# tongueboard.net
KiCad netlist of a schematic drawn in EAGLE
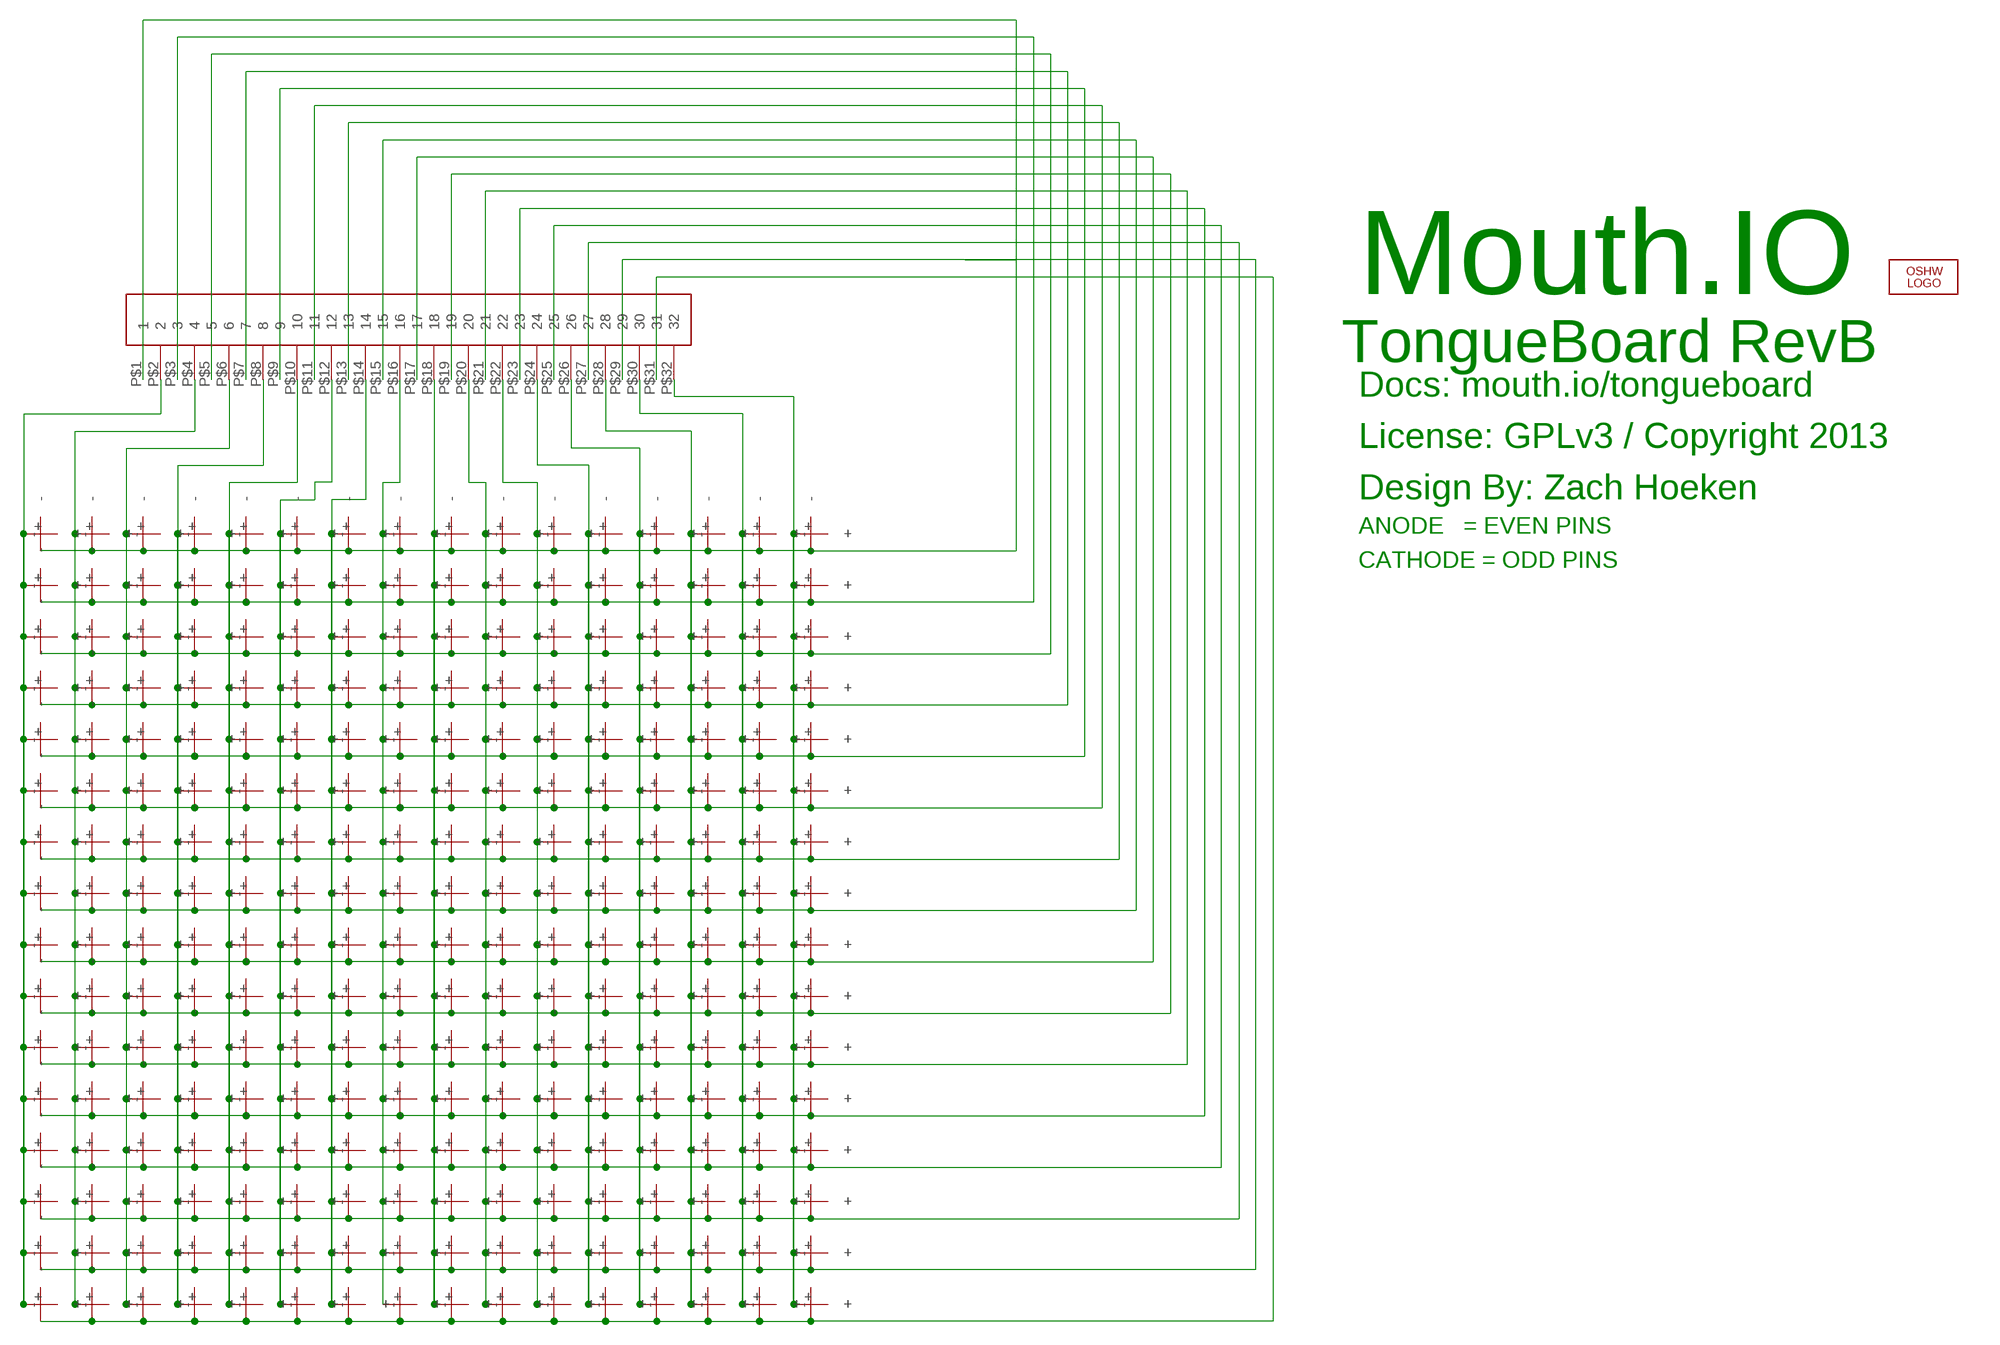
[diagram p0: schematic, sheet 1]

(export (version "E")
  (design (tool "Eeschema 10.0.6"))
  (components
    (comp (ref "LOGO1")
      (value "OSHW_LOGO_10MIL")
      (footprint "eagle-import:OSHW_10X500_NOTEXT_COPPER")
      (libsource (lib "eagle-import") (part "OSHW_LOGO_10MIL"))
    )
    (comp (ref "U$1")
      (value "ELECTRODE60MIL")
      (footprint "eagle-import:61MIL")
      (libsource (lib "eagle-import") (part "ELECTRODE60MIL"))
    )
    (comp (ref "U$2")
      (value "ELECTRODE60MIL")
      (footprint "eagle-import:61MIL")
      (libsource (lib "eagle-import") (part "ELECTRODE60MIL"))
    )
    (comp (ref "U$3")
      (value "ELECTRODE60MIL")
      (footprint "eagle-import:61MIL")
      (libsource (lib "eagle-import") (part "ELECTRODE60MIL"))
    )
    (comp (ref "U$4")
      (value "ELECTRODE60MIL")
      (footprint "eagle-import:61MIL")
      (libsource (lib "eagle-import") (part "ELECTRODE60MIL"))
    )
    (comp (ref "U$5")
      (value "ELECTRODE60MIL")
      (footprint "eagle-import:61MIL")
      (libsource (lib "eagle-import") (part "ELECTRODE60MIL"))
    )
    (comp (ref "U$6")
      (value "ELECTRODE60MIL")
      (footprint "eagle-import:61MIL")
      (libsource (lib "eagle-import") (part "ELECTRODE60MIL"))
    )
    (comp (ref "U$7")
      (value "ELECTRODE60MIL")
      (footprint "eagle-import:61MIL")
      (libsource (lib "eagle-import") (part "ELECTRODE60MIL"))
    )
    (comp (ref "U$8")
      (value "ELECTRODE60MIL")
      (footprint "eagle-import:61MIL")
      (libsource (lib "eagle-import") (part "ELECTRODE60MIL"))
    )
    (comp (ref "U$9")
      (value "ELECTRODE60MIL")
      (footprint "eagle-import:61MIL")
      (libsource (lib "eagle-import") (part "ELECTRODE60MIL"))
    )
    (comp (ref "U$10")
      (value "ELECTRODE60MIL")
      (footprint "eagle-import:61MIL")
      (libsource (lib "eagle-import") (part "ELECTRODE60MIL"))
    )
    (comp (ref "U$11")
      (value "ELECTRODE60MIL")
      (footprint "eagle-import:61MIL")
      (libsource (lib "eagle-import") (part "ELECTRODE60MIL"))
    )
    (comp (ref "U$12")
      (value "ELECTRODE60MIL")
      (footprint "eagle-import:61MIL")
      (libsource (lib "eagle-import") (part "ELECTRODE60MIL"))
    )
    (comp (ref "U$13")
      (value "ELECTRODE60MIL")
      (footprint "eagle-import:61MIL")
      (libsource (lib "eagle-import") (part "ELECTRODE60MIL"))
    )
    (comp (ref "U$14")
      (value "ELECTRODE60MIL")
      (footprint "eagle-import:61MIL")
      (libsource (lib "eagle-import") (part "ELECTRODE60MIL"))
    )
    (comp (ref "U$15")
      (value "ELECTRODE60MIL")
      (footprint "eagle-import:61MIL")
      (libsource (lib "eagle-import") (part "ELECTRODE60MIL"))
    )
    (comp (ref "U$16")
      (value "ELECTRODE61MILJCT")
      (footprint "eagle-import:61MILJCT")
      (libsource (lib "eagle-import") (part "ELECTRODE61MILJCT"))
    )
    (comp (ref "U$17")
      (value "ELECTRODE60MIL")
      (footprint "eagle-import:61MIL")
      (libsource (lib "eagle-import") (part "ELECTRODE60MIL"))
    )
    (comp (ref "U$18")
      (value "ELECTRODE60MIL")
      (footprint "eagle-import:61MIL")
      (libsource (lib "eagle-import") (part "ELECTRODE60MIL"))
    )
    (comp (ref "U$19")
      (value "ELECTRODE60MIL")
      (footprint "eagle-import:61MIL")
      (libsource (lib "eagle-import") (part "ELECTRODE60MIL"))
    )
    (comp (ref "U$20")
      (value "ELECTRODE60MIL")
      (footprint "eagle-import:61MIL")
      (libsource (lib "eagle-import") (part "ELECTRODE60MIL"))
    )
    (comp (ref "U$21")
      (value "ELECTRODE60MIL")
      (footprint "eagle-import:61MIL")
      (libsource (lib "eagle-import") (part "ELECTRODE60MIL"))
    )
    (comp (ref "U$22")
      (value "ELECTRODE60MIL")
      (footprint "eagle-import:61MIL")
      (libsource (lib "eagle-import") (part "ELECTRODE60MIL"))
    )
    (comp (ref "U$23")
      (value "ELECTRODE60MIL")
      (footprint "eagle-import:61MIL")
      (libsource (lib "eagle-import") (part "ELECTRODE60MIL"))
    )
    (comp (ref "U$24")
      (value "ELECTRODE60MIL")
      (footprint "eagle-import:61MIL")
      (libsource (lib "eagle-import") (part "ELECTRODE60MIL"))
    )
    (comp (ref "U$25")
      (value "ELECTRODE60MIL")
      (footprint "eagle-import:61MIL")
      (libsource (lib "eagle-import") (part "ELECTRODE60MIL"))
    )
    (comp (ref "U$26")
      (value "ELECTRODE60MIL")
      (footprint "eagle-import:61MIL")
      (libsource (lib "eagle-import") (part "ELECTRODE60MIL"))
    )
    (comp (ref "U$27")
      (value "ELECTRODE60MIL")
      (footprint "eagle-import:61MIL")
      (libsource (lib "eagle-import") (part "ELECTRODE60MIL"))
    )
    (comp (ref "U$28")
      (value "ELECTRODE60MIL")
      (footprint "eagle-import:61MIL")
      (libsource (lib "eagle-import") (part "ELECTRODE60MIL"))
    )
    (comp (ref "U$29")
      (value "ELECTRODE60MIL")
      (footprint "eagle-import:61MIL")
      (libsource (lib "eagle-import") (part "ELECTRODE60MIL"))
    )
    (comp (ref "U$30")
      (value "ELECTRODE60MIL")
      (footprint "eagle-import:61MIL")
      (libsource (lib "eagle-import") (part "ELECTRODE60MIL"))
    )
    (comp (ref "U$31")
      (value "ELECTRODE61MILJCT")
      (footprint "eagle-import:61MILJCT")
      (libsource (lib "eagle-import") (part "ELECTRODE61MILJCT"))
    )
    (comp (ref "U$32")
      (value "ELECTRODE60MIL")
      (footprint "eagle-import:61MIL")
      (libsource (lib "eagle-import") (part "ELECTRODE60MIL"))
    )
    (comp (ref "U$33")
      (value "ELECTRODE60MIL")
      (footprint "eagle-import:61MIL")
      (libsource (lib "eagle-import") (part "ELECTRODE60MIL"))
    )
    (comp (ref "U$34")
      (value "ELECTRODE60MIL")
      (footprint "eagle-import:61MIL")
      (libsource (lib "eagle-import") (part "ELECTRODE60MIL"))
    )
    (comp (ref "U$35")
      (value "ELECTRODE60MIL")
      (footprint "eagle-import:61MIL")
      (libsource (lib "eagle-import") (part "ELECTRODE60MIL"))
    )
    (comp (ref "U$36")
      (value "ELECTRODE60MIL")
      (footprint "eagle-import:61MIL")
      (libsource (lib "eagle-import") (part "ELECTRODE60MIL"))
    )
    (comp (ref "U$37")
      (value "ELECTRODE60MIL")
      (footprint "eagle-import:61MIL")
      (libsource (lib "eagle-import") (part "ELECTRODE60MIL"))
    )
    (comp (ref "U$38")
      (value "ELECTRODE60MIL")
      (footprint "eagle-import:61MIL")
      (libsource (lib "eagle-import") (part "ELECTRODE60MIL"))
    )
    (comp (ref "U$39")
      (value "ELECTRODE60MIL")
      (footprint "eagle-import:61MIL")
      (libsource (lib "eagle-import") (part "ELECTRODE60MIL"))
    )
    (comp (ref "U$40")
      (value "ELECTRODE60MIL")
      (footprint "eagle-import:61MIL")
      (libsource (lib "eagle-import") (part "ELECTRODE60MIL"))
    )
    (comp (ref "U$41")
      (value "ELECTRODE60MIL")
      (footprint "eagle-import:61MIL")
      (libsource (lib "eagle-import") (part "ELECTRODE60MIL"))
    )
    (comp (ref "U$42")
      (value "ELECTRODE60MIL")
      (footprint "eagle-import:61MIL")
      (libsource (lib "eagle-import") (part "ELECTRODE60MIL"))
    )
    (comp (ref "U$43")
      (value "ELECTRODE60MIL")
      (footprint "eagle-import:61MIL")
      (libsource (lib "eagle-import") (part "ELECTRODE60MIL"))
    )
    (comp (ref "U$44")
      (value "ELECTRODE60MIL")
      (footprint "eagle-import:61MIL")
      (libsource (lib "eagle-import") (part "ELECTRODE60MIL"))
    )
    (comp (ref "U$45")
      (value "ELECTRODE60MIL")
      (footprint "eagle-import:61MIL")
      (libsource (lib "eagle-import") (part "ELECTRODE60MIL"))
    )
    (comp (ref "U$46")
      (value "ELECTRODE61MILJCT")
      (footprint "eagle-import:61MILJCT")
      (libsource (lib "eagle-import") (part "ELECTRODE61MILJCT"))
    )
    (comp (ref "U$47")
      (value "ELECTRODE60MIL")
      (footprint "eagle-import:61MIL")
      (libsource (lib "eagle-import") (part "ELECTRODE60MIL"))
    )
    (comp (ref "U$48")
      (value "ELECTRODE60MIL")
      (footprint "eagle-import:61MIL")
      (libsource (lib "eagle-import") (part "ELECTRODE60MIL"))
    )
    (comp (ref "U$49")
      (value "ELECTRODE60MIL")
      (footprint "eagle-import:61MIL")
      (libsource (lib "eagle-import") (part "ELECTRODE60MIL"))
    )
    (comp (ref "U$50")
      (value "ELECTRODE60MIL")
      (footprint "eagle-import:61MIL")
      (libsource (lib "eagle-import") (part "ELECTRODE60MIL"))
    )
    (comp (ref "U$51")
      (value "ELECTRODE60MIL")
      (footprint "eagle-import:61MIL")
      (libsource (lib "eagle-import") (part "ELECTRODE60MIL"))
    )
    (comp (ref "U$52")
      (value "ELECTRODE60MIL")
      (footprint "eagle-import:61MIL")
      (libsource (lib "eagle-import") (part "ELECTRODE60MIL"))
    )
    (comp (ref "U$53")
      (value "ELECTRODE60MIL")
      (footprint "eagle-import:61MIL")
      (libsource (lib "eagle-import") (part "ELECTRODE60MIL"))
    )
    (comp (ref "U$54")
      (value "ELECTRODE60MIL")
      (footprint "eagle-import:61MIL")
      (libsource (lib "eagle-import") (part "ELECTRODE60MIL"))
    )
    (comp (ref "U$55")
      (value "ELECTRODE60MIL")
      (footprint "eagle-import:61MIL")
      (libsource (lib "eagle-import") (part "ELECTRODE60MIL"))
    )
    (comp (ref "U$56")
      (value "ELECTRODE60MIL")
      (footprint "eagle-import:61MIL")
      (libsource (lib "eagle-import") (part "ELECTRODE60MIL"))
    )
    (comp (ref "U$57")
      (value "ELECTRODE60MIL")
      (footprint "eagle-import:61MIL")
      (libsource (lib "eagle-import") (part "ELECTRODE60MIL"))
    )
    (comp (ref "U$58")
      (value "ELECTRODE60MIL")
      (footprint "eagle-import:61MIL")
      (libsource (lib "eagle-import") (part "ELECTRODE60MIL"))
    )
    (comp (ref "U$59")
      (value "ELECTRODE60MIL")
      (footprint "eagle-import:61MIL")
      (libsource (lib "eagle-import") (part "ELECTRODE60MIL"))
    )
    (comp (ref "U$60")
      (value "ELECTRODE60MIL")
      (footprint "eagle-import:61MIL")
      (libsource (lib "eagle-import") (part "ELECTRODE60MIL"))
    )
    (comp (ref "U$61")
      (value "ELECTRODE61MILJCT")
      (footprint "eagle-import:61MILJCT")
      (libsource (lib "eagle-import") (part "ELECTRODE61MILJCT"))
    )
    (comp (ref "U$62")
      (value "ELECTRODE60MIL")
      (footprint "eagle-import:61MIL")
      (libsource (lib "eagle-import") (part "ELECTRODE60MIL"))
    )
    (comp (ref "U$63")
      (value "ELECTRODE60MIL")
      (footprint "eagle-import:61MIL")
      (libsource (lib "eagle-import") (part "ELECTRODE60MIL"))
    )
    (comp (ref "U$64")
      (value "ELECTRODE60MIL")
      (footprint "eagle-import:61MIL")
      (libsource (lib "eagle-import") (part "ELECTRODE60MIL"))
    )
    (comp (ref "U$65")
      (value "ELECTRODE60MIL")
      (footprint "eagle-import:61MIL")
      (libsource (lib "eagle-import") (part "ELECTRODE60MIL"))
    )
    (comp (ref "U$66")
      (value "ELECTRODE60MIL")
      (footprint "eagle-import:61MIL")
      (libsource (lib "eagle-import") (part "ELECTRODE60MIL"))
    )
    (comp (ref "U$67")
      (value "ELECTRODE60MIL")
      (footprint "eagle-import:61MIL")
      (libsource (lib "eagle-import") (part "ELECTRODE60MIL"))
    )
    (comp (ref "U$68")
      (value "ELECTRODE60MIL")
      (footprint "eagle-import:61MIL")
      (libsource (lib "eagle-import") (part "ELECTRODE60MIL"))
    )
    (comp (ref "U$69")
      (value "ELECTRODE60MIL")
      (footprint "eagle-import:61MIL")
      (libsource (lib "eagle-import") (part "ELECTRODE60MIL"))
    )
    (comp (ref "U$70")
      (value "ELECTRODE60MIL")
      (footprint "eagle-import:61MIL")
      (libsource (lib "eagle-import") (part "ELECTRODE60MIL"))
    )
    (comp (ref "U$71")
      (value "ELECTRODE60MIL")
      (footprint "eagle-import:61MIL")
      (libsource (lib "eagle-import") (part "ELECTRODE60MIL"))
    )
    (comp (ref "U$72")
      (value "ELECTRODE60MIL")
      (footprint "eagle-import:61MIL")
      (libsource (lib "eagle-import") (part "ELECTRODE60MIL"))
    )
    (comp (ref "U$73")
      (value "ELECTRODE60MIL")
      (footprint "eagle-import:61MIL")
      (libsource (lib "eagle-import") (part "ELECTRODE60MIL"))
    )
    (comp (ref "U$74")
      (value "ELECTRODE60MIL")
      (footprint "eagle-import:61MIL")
      (libsource (lib "eagle-import") (part "ELECTRODE60MIL"))
    )
    (comp (ref "U$75")
      (value "ELECTRODE60MIL")
      (footprint "eagle-import:61MIL")
      (libsource (lib "eagle-import") (part "ELECTRODE60MIL"))
    )
    (comp (ref "U$76")
      (value "ELECTRODE61MILJCT")
      (footprint "eagle-import:61MILJCT")
      (libsource (lib "eagle-import") (part "ELECTRODE61MILJCT"))
    )
    (comp (ref "U$77")
      (value "ELECTRODE60MIL")
      (footprint "eagle-import:61MIL")
      (libsource (lib "eagle-import") (part "ELECTRODE60MIL"))
    )
    (comp (ref "U$78")
      (value "ELECTRODE60MIL")
      (footprint "eagle-import:61MIL")
      (libsource (lib "eagle-import") (part "ELECTRODE60MIL"))
    )
    (comp (ref "U$79")
      (value "ELECTRODE60MIL")
      (footprint "eagle-import:61MIL")
      (libsource (lib "eagle-import") (part "ELECTRODE60MIL"))
    )
    (comp (ref "U$80")
      (value "ELECTRODE60MIL")
      (footprint "eagle-import:61MIL")
      (libsource (lib "eagle-import") (part "ELECTRODE60MIL"))
    )
    (comp (ref "U$81")
      (value "ELECTRODE60MIL")
      (footprint "eagle-import:61MIL")
      (libsource (lib "eagle-import") (part "ELECTRODE60MIL"))
    )
    (comp (ref "U$82")
      (value "ELECTRODE60MIL")
      (footprint "eagle-import:61MIL")
      (libsource (lib "eagle-import") (part "ELECTRODE60MIL"))
    )
    (comp (ref "U$83")
      (value "ELECTRODE60MIL")
      (footprint "eagle-import:61MIL")
      (libsource (lib "eagle-import") (part "ELECTRODE60MIL"))
    )
    (comp (ref "U$84")
      (value "ELECTRODE60MIL")
      (footprint "eagle-import:61MIL")
      (libsource (lib "eagle-import") (part "ELECTRODE60MIL"))
    )
    (comp (ref "U$85")
      (value "ELECTRODE60MIL")
      (footprint "eagle-import:61MIL")
      (libsource (lib "eagle-import") (part "ELECTRODE60MIL"))
    )
    (comp (ref "U$86")
      (value "ELECTRODE60MIL")
      (footprint "eagle-import:61MIL")
      (libsource (lib "eagle-import") (part "ELECTRODE60MIL"))
    )
    (comp (ref "U$87")
      (value "ELECTRODE60MIL")
      (footprint "eagle-import:61MIL")
      (libsource (lib "eagle-import") (part "ELECTRODE60MIL"))
    )
    (comp (ref "U$88")
      (value "ELECTRODE60MIL")
      (footprint "eagle-import:61MIL")
      (libsource (lib "eagle-import") (part "ELECTRODE60MIL"))
    )
    (comp (ref "U$89")
      (value "ELECTRODE60MIL")
      (footprint "eagle-import:61MIL")
      (libsource (lib "eagle-import") (part "ELECTRODE60MIL"))
    )
    (comp (ref "U$90")
      (value "ELECTRODE60MIL")
      (footprint "eagle-import:61MIL")
      (libsource (lib "eagle-import") (part "ELECTRODE60MIL"))
    )
    (comp (ref "U$91")
      (value "ELECTRODE61MILJCT")
      (footprint "eagle-import:61MILJCT")
      (libsource (lib "eagle-import") (part "ELECTRODE61MILJCT"))
    )
    (comp (ref "U$92")
      (value "ELECTRODE60MIL")
      (footprint "eagle-import:61MIL")
      (libsource (lib "eagle-import") (part "ELECTRODE60MIL"))
    )
    (comp (ref "U$93")
      (value "ELECTRODE60MIL")
      (footprint "eagle-import:61MIL")
      (libsource (lib "eagle-import") (part "ELECTRODE60MIL"))
    )
    (comp (ref "U$94")
      (value "ELECTRODE60MIL")
      (footprint "eagle-import:61MIL")
      (libsource (lib "eagle-import") (part "ELECTRODE60MIL"))
    )
    (comp (ref "U$95")
      (value "ELECTRODE60MIL")
      (footprint "eagle-import:61MIL")
      (libsource (lib "eagle-import") (part "ELECTRODE60MIL"))
    )
    (comp (ref "U$96")
      (value "ELECTRODE60MIL")
      (footprint "eagle-import:61MIL")
      (libsource (lib "eagle-import") (part "ELECTRODE60MIL"))
    )
    (comp (ref "U$97")
      (value "ELECTRODE60MIL")
      (footprint "eagle-import:61MIL")
      (libsource (lib "eagle-import") (part "ELECTRODE60MIL"))
    )
    (comp (ref "U$98")
      (value "ELECTRODE60MIL")
      (footprint "eagle-import:61MIL")
      (libsource (lib "eagle-import") (part "ELECTRODE60MIL"))
    )
    (comp (ref "U$99")
      (value "ELECTRODE60MIL")
      (footprint "eagle-import:61MIL")
      (libsource (lib "eagle-import") (part "ELECTRODE60MIL"))
    )
    (comp (ref "U$100")
      (value "ELECTRODE60MIL")
      (footprint "eagle-import:61MIL")
      (libsource (lib "eagle-import") (part "ELECTRODE60MIL"))
    )
    (comp (ref "U$101")
      (value "ELECTRODE60MIL")
      (footprint "eagle-import:61MIL")
      (libsource (lib "eagle-import") (part "ELECTRODE60MIL"))
    )
    (comp (ref "U$102")
      (value "ELECTRODE60MIL")
      (footprint "eagle-import:61MIL")
      (libsource (lib "eagle-import") (part "ELECTRODE60MIL"))
    )
    (comp (ref "U$103")
      (value "ELECTRODE60MIL")
      (footprint "eagle-import:61MIL")
      (libsource (lib "eagle-import") (part "ELECTRODE60MIL"))
    )
    (comp (ref "U$104")
      (value "ELECTRODE60MIL")
      (footprint "eagle-import:61MIL")
      (libsource (lib "eagle-import") (part "ELECTRODE60MIL"))
    )
    (comp (ref "U$105")
      (value "ELECTRODE60MIL")
      (footprint "eagle-import:61MIL")
      (libsource (lib "eagle-import") (part "ELECTRODE60MIL"))
    )
    (comp (ref "U$106")
      (value "ELECTRODE61MILJCT")
      (footprint "eagle-import:61MILJCT")
      (libsource (lib "eagle-import") (part "ELECTRODE61MILJCT"))
    )
    (comp (ref "U$107")
      (value "ELECTRODE60MIL")
      (footprint "eagle-import:61MIL")
      (libsource (lib "eagle-import") (part "ELECTRODE60MIL"))
    )
    (comp (ref "U$108")
      (value "ELECTRODE60MIL")
      (footprint "eagle-import:61MIL")
      (libsource (lib "eagle-import") (part "ELECTRODE60MIL"))
    )
    (comp (ref "U$109")
      (value "ELECTRODE60MIL")
      (footprint "eagle-import:61MIL")
      (libsource (lib "eagle-import") (part "ELECTRODE60MIL"))
    )
    (comp (ref "U$110")
      (value "ELECTRODE60MIL")
      (footprint "eagle-import:61MIL")
      (libsource (lib "eagle-import") (part "ELECTRODE60MIL"))
    )
    (comp (ref "U$111")
      (value "ELECTRODE60MIL")
      (footprint "eagle-import:61MIL")
      (libsource (lib "eagle-import") (part "ELECTRODE60MIL"))
    )
    (comp (ref "U$112")
      (value "ELECTRODE60MIL")
      (footprint "eagle-import:61MIL")
      (libsource (lib "eagle-import") (part "ELECTRODE60MIL"))
    )
    (comp (ref "U$113")
      (value "ELECTRODE60MIL")
      (footprint "eagle-import:61MIL")
      (libsource (lib "eagle-import") (part "ELECTRODE60MIL"))
    )
    (comp (ref "U$114")
      (value "ELECTRODE60MIL")
      (footprint "eagle-import:61MIL")
      (libsource (lib "eagle-import") (part "ELECTRODE60MIL"))
    )
    (comp (ref "U$115")
      (value "ELECTRODE60MIL")
      (footprint "eagle-import:61MIL")
      (libsource (lib "eagle-import") (part "ELECTRODE60MIL"))
    )
    (comp (ref "U$116")
      (value "ELECTRODE60MIL")
      (footprint "eagle-import:61MIL")
      (libsource (lib "eagle-import") (part "ELECTRODE60MIL"))
    )
    (comp (ref "U$117")
      (value "ELECTRODE60MIL")
      (footprint "eagle-import:61MIL")
      (libsource (lib "eagle-import") (part "ELECTRODE60MIL"))
    )
    (comp (ref "U$118")
      (value "ELECTRODE60MIL")
      (footprint "eagle-import:61MIL")
      (libsource (lib "eagle-import") (part "ELECTRODE60MIL"))
    )
    (comp (ref "U$119")
      (value "ELECTRODE60MIL")
      (footprint "eagle-import:61MIL")
      (libsource (lib "eagle-import") (part "ELECTRODE60MIL"))
    )
    (comp (ref "U$120")
      (value "ELECTRODE60MIL")
      (footprint "eagle-import:61MIL")
      (libsource (lib "eagle-import") (part "ELECTRODE60MIL"))
    )
    (comp (ref "U$121")
      (value "ELECTRODE61MILJCT")
      (footprint "eagle-import:61MILJCT")
      (libsource (lib "eagle-import") (part "ELECTRODE61MILJCT"))
    )
    (comp (ref "U$122")
      (value "ELECTRODE60MIL")
      (footprint "eagle-import:61MIL")
      (libsource (lib "eagle-import") (part "ELECTRODE60MIL"))
    )
    (comp (ref "U$123")
      (value "ELECTRODE60MIL")
      (footprint "eagle-import:61MIL")
      (libsource (lib "eagle-import") (part "ELECTRODE60MIL"))
    )
    (comp (ref "U$124")
      (value "ELECTRODE60MIL")
      (footprint "eagle-import:61MIL")
      (libsource (lib "eagle-import") (part "ELECTRODE60MIL"))
    )
    (comp (ref "U$125")
      (value "ELECTRODE60MIL")
      (footprint "eagle-import:61MIL")
      (libsource (lib "eagle-import") (part "ELECTRODE60MIL"))
    )
    (comp (ref "U$126")
      (value "ELECTRODE60MIL")
      (footprint "eagle-import:61MIL")
      (libsource (lib "eagle-import") (part "ELECTRODE60MIL"))
    )
    (comp (ref "U$127")
      (value "ELECTRODE60MIL")
      (footprint "eagle-import:61MIL")
      (libsource (lib "eagle-import") (part "ELECTRODE60MIL"))
    )
    (comp (ref "U$128")
      (value "ELECTRODE60MIL")
      (footprint "eagle-import:61MIL")
      (libsource (lib "eagle-import") (part "ELECTRODE60MIL"))
    )
    (comp (ref "U$129")
      (value "ELECTRODE60MIL")
      (footprint "eagle-import:61MIL")
      (libsource (lib "eagle-import") (part "ELECTRODE60MIL"))
    )
    (comp (ref "U$130")
      (value "ELECTRODE60MIL")
      (footprint "eagle-import:61MIL")
      (libsource (lib "eagle-import") (part "ELECTRODE60MIL"))
    )
    (comp (ref "U$131")
      (value "ELECTRODE60MIL")
      (footprint "eagle-import:61MIL")
      (libsource (lib "eagle-import") (part "ELECTRODE60MIL"))
    )
    (comp (ref "U$132")
      (value "ELECTRODE60MIL")
      (footprint "eagle-import:61MIL")
      (libsource (lib "eagle-import") (part "ELECTRODE60MIL"))
    )
    (comp (ref "U$133")
      (value "ELECTRODE60MIL")
      (footprint "eagle-import:61MIL")
      (libsource (lib "eagle-import") (part "ELECTRODE60MIL"))
    )
    (comp (ref "U$134")
      (value "ELECTRODE60MIL")
      (footprint "eagle-import:61MIL")
      (libsource (lib "eagle-import") (part "ELECTRODE60MIL"))
    )
    (comp (ref "U$135")
      (value "ELECTRODE60MIL")
      (footprint "eagle-import:61MIL")
      (libsource (lib "eagle-import") (part "ELECTRODE60MIL"))
    )
    (comp (ref "U$136")
      (value "ELECTRODE61MILJCT")
      (footprint "eagle-import:61MILJCT")
      (libsource (lib "eagle-import") (part "ELECTRODE61MILJCT"))
    )
    (comp (ref "U$137")
      (value "ELECTRODE60MIL")
      (footprint "eagle-import:61MIL")
      (libsource (lib "eagle-import") (part "ELECTRODE60MIL"))
    )
    (comp (ref "U$138")
      (value "ELECTRODE60MIL")
      (footprint "eagle-import:61MIL")
      (libsource (lib "eagle-import") (part "ELECTRODE60MIL"))
    )
    (comp (ref "U$139")
      (value "ELECTRODE60MIL")
      (footprint "eagle-import:61MIL")
      (libsource (lib "eagle-import") (part "ELECTRODE60MIL"))
    )
    (comp (ref "U$140")
      (value "ELECTRODE60MIL")
      (footprint "eagle-import:61MIL")
      (libsource (lib "eagle-import") (part "ELECTRODE60MIL"))
    )
    (comp (ref "U$141")
      (value "ELECTRODE60MIL")
      (footprint "eagle-import:61MIL")
      (libsource (lib "eagle-import") (part "ELECTRODE60MIL"))
    )
    (comp (ref "U$142")
      (value "ELECTRODE60MIL")
      (footprint "eagle-import:61MIL")
      (libsource (lib "eagle-import") (part "ELECTRODE60MIL"))
    )
    (comp (ref "U$143")
      (value "ELECTRODE60MIL")
      (footprint "eagle-import:61MIL")
      (libsource (lib "eagle-import") (part "ELECTRODE60MIL"))
    )
    (comp (ref "U$144")
      (value "ELECTRODE60MIL")
      (footprint "eagle-import:61MIL")
      (libsource (lib "eagle-import") (part "ELECTRODE60MIL"))
    )
    (comp (ref "U$145")
      (value "ELECTRODE60MIL")
      (footprint "eagle-import:61MIL")
      (libsource (lib "eagle-import") (part "ELECTRODE60MIL"))
    )
    (comp (ref "U$146")
      (value "ELECTRODE60MIL")
      (footprint "eagle-import:61MIL")
      (libsource (lib "eagle-import") (part "ELECTRODE60MIL"))
    )
    (comp (ref "U$147")
      (value "ELECTRODE60MIL")
      (footprint "eagle-import:61MIL")
      (libsource (lib "eagle-import") (part "ELECTRODE60MIL"))
    )
    (comp (ref "U$148")
      (value "ELECTRODE60MIL")
      (footprint "eagle-import:61MIL")
      (libsource (lib "eagle-import") (part "ELECTRODE60MIL"))
    )
    (comp (ref "U$149")
      (value "ELECTRODE60MIL")
      (footprint "eagle-import:61MIL")
      (libsource (lib "eagle-import") (part "ELECTRODE60MIL"))
    )
    (comp (ref "U$150")
      (value "ELECTRODE60MIL")
      (footprint "eagle-import:61MIL")
      (libsource (lib "eagle-import") (part "ELECTRODE60MIL"))
    )
    (comp (ref "U$151")
      (value "ELECTRODE61MILJCT")
      (footprint "eagle-import:61MILJCT")
      (libsource (lib "eagle-import") (part "ELECTRODE61MILJCT"))
    )
    (comp (ref "U$152")
      (value "ELECTRODE60MIL")
      (footprint "eagle-import:61MIL")
      (libsource (lib "eagle-import") (part "ELECTRODE60MIL"))
    )
    (comp (ref "U$153")
      (value "ELECTRODE60MIL")
      (footprint "eagle-import:61MIL")
      (libsource (lib "eagle-import") (part "ELECTRODE60MIL"))
    )
    (comp (ref "U$154")
      (value "ELECTRODE60MIL")
      (footprint "eagle-import:61MIL")
      (libsource (lib "eagle-import") (part "ELECTRODE60MIL"))
    )
    (comp (ref "U$155")
      (value "ELECTRODE60MIL")
      (footprint "eagle-import:61MIL")
      (libsource (lib "eagle-import") (part "ELECTRODE60MIL"))
    )
    (comp (ref "U$156")
      (value "ELECTRODE60MIL")
      (footprint "eagle-import:61MIL")
      (libsource (lib "eagle-import") (part "ELECTRODE60MIL"))
    )
    (comp (ref "U$157")
      (value "ELECTRODE60MIL")
      (footprint "eagle-import:61MIL")
      (libsource (lib "eagle-import") (part "ELECTRODE60MIL"))
    )
    (comp (ref "U$158")
      (value "ELECTRODE60MIL")
      (footprint "eagle-import:61MIL")
      (libsource (lib "eagle-import") (part "ELECTRODE60MIL"))
    )
    (comp (ref "U$159")
      (value "ELECTRODE60MIL")
      (footprint "eagle-import:61MIL")
      (libsource (lib "eagle-import") (part "ELECTRODE60MIL"))
    )
    (comp (ref "U$160")
      (value "ELECTRODE60MIL")
      (footprint "eagle-import:61MIL")
      (libsource (lib "eagle-import") (part "ELECTRODE60MIL"))
    )
    (comp (ref "U$161")
      (value "ELECTRODE60MIL")
      (footprint "eagle-import:61MIL")
      (libsource (lib "eagle-import") (part "ELECTRODE60MIL"))
    )
    (comp (ref "U$162")
      (value "ELECTRODE60MIL")
      (footprint "eagle-import:61MIL")
      (libsource (lib "eagle-import") (part "ELECTRODE60MIL"))
    )
    (comp (ref "U$163")
      (value "ELECTRODE60MIL")
      (footprint "eagle-import:61MIL")
      (libsource (lib "eagle-import") (part "ELECTRODE60MIL"))
    )
    (comp (ref "U$164")
      (value "ELECTRODE60MIL")
      (footprint "eagle-import:61MIL")
      (libsource (lib "eagle-import") (part "ELECTRODE60MIL"))
    )
    (comp (ref "U$165")
      (value "ELECTRODE60MIL")
      (footprint "eagle-import:61MIL")
      (libsource (lib "eagle-import") (part "ELECTRODE60MIL"))
    )
    (comp (ref "U$166")
      (value "ELECTRODE61MILJCT")
      (footprint "eagle-import:61MILJCT")
      (libsource (lib "eagle-import") (part "ELECTRODE61MILJCT"))
    )
    (comp (ref "U$167")
      (value "ELECTRODE60MIL")
      (footprint "eagle-import:61MIL")
      (libsource (lib "eagle-import") (part "ELECTRODE60MIL"))
    )
    (comp (ref "U$168")
      (value "ELECTRODE60MIL")
      (footprint "eagle-import:61MIL")
      (libsource (lib "eagle-import") (part "ELECTRODE60MIL"))
    )
    (comp (ref "U$169")
      (value "ELECTRODE60MIL")
      (footprint "eagle-import:61MIL")
      (libsource (lib "eagle-import") (part "ELECTRODE60MIL"))
    )
    (comp (ref "U$170")
      (value "ELECTRODE60MIL")
      (footprint "eagle-import:61MIL")
      (libsource (lib "eagle-import") (part "ELECTRODE60MIL"))
    )
    (comp (ref "U$171")
      (value "ELECTRODE60MIL")
      (footprint "eagle-import:61MIL")
      (libsource (lib "eagle-import") (part "ELECTRODE60MIL"))
    )
    (comp (ref "U$172")
      (value "ELECTRODE60MIL")
      (footprint "eagle-import:61MIL")
      (libsource (lib "eagle-import") (part "ELECTRODE60MIL"))
    )
    (comp (ref "U$173")
      (value "ELECTRODE60MIL")
      (footprint "eagle-import:61MIL")
      (libsource (lib "eagle-import") (part "ELECTRODE60MIL"))
    )
    (comp (ref "U$174")
      (value "ELECTRODE60MIL")
      (footprint "eagle-import:61MIL")
      (libsource (lib "eagle-import") (part "ELECTRODE60MIL"))
    )
    (comp (ref "U$175")
      (value "ELECTRODE60MIL")
      (footprint "eagle-import:61MIL")
      (libsource (lib "eagle-import") (part "ELECTRODE60MIL"))
    )
    (comp (ref "U$176")
      (value "ELECTRODE60MIL")
      (footprint "eagle-import:61MIL")
      (libsource (lib "eagle-import") (part "ELECTRODE60MIL"))
    )
    (comp (ref "U$177")
      (value "ELECTRODE60MIL")
      (footprint "eagle-import:61MIL")
      (libsource (lib "eagle-import") (part "ELECTRODE60MIL"))
    )
    (comp (ref "U$178")
      (value "ELECTRODE60MIL")
      (footprint "eagle-import:61MIL")
      (libsource (lib "eagle-import") (part "ELECTRODE60MIL"))
    )
    (comp (ref "U$179")
      (value "ELECTRODE60MIL")
      (footprint "eagle-import:61MIL")
      (libsource (lib "eagle-import") (part "ELECTRODE60MIL"))
    )
    (comp (ref "U$180")
      (value "ELECTRODE60MIL")
      (footprint "eagle-import:61MIL")
      (libsource (lib "eagle-import") (part "ELECTRODE60MIL"))
    )
    (comp (ref "U$181")
      (value "ELECTRODE61MILJCT")
      (footprint "eagle-import:61MILJCT")
      (libsource (lib "eagle-import") (part "ELECTRODE61MILJCT"))
    )
    (comp (ref "U$182")
      (value "ELECTRODE60MIL")
      (footprint "eagle-import:61MIL")
      (libsource (lib "eagle-import") (part "ELECTRODE60MIL"))
    )
    (comp (ref "U$183")
      (value "ELECTRODE60MIL")
      (footprint "eagle-import:61MIL")
      (libsource (lib "eagle-import") (part "ELECTRODE60MIL"))
    )
    (comp (ref "U$184")
      (value "ELECTRODE60MIL")
      (footprint "eagle-import:61MIL")
      (libsource (lib "eagle-import") (part "ELECTRODE60MIL"))
    )
    (comp (ref "U$185")
      (value "ELECTRODE60MIL")
      (footprint "eagle-import:61MIL")
      (libsource (lib "eagle-import") (part "ELECTRODE60MIL"))
    )
    (comp (ref "U$186")
      (value "ELECTRODE60MIL")
      (footprint "eagle-import:61MIL")
      (libsource (lib "eagle-import") (part "ELECTRODE60MIL"))
    )
    (comp (ref "U$187")
      (value "ELECTRODE60MIL")
      (footprint "eagle-import:61MIL")
      (libsource (lib "eagle-import") (part "ELECTRODE60MIL"))
    )
    (comp (ref "U$188")
      (value "ELECTRODE60MIL")
      (footprint "eagle-import:61MIL")
      (libsource (lib "eagle-import") (part "ELECTRODE60MIL"))
    )
    (comp (ref "U$189")
      (value "ELECTRODE60MIL")
      (footprint "eagle-import:61MIL")
      (libsource (lib "eagle-import") (part "ELECTRODE60MIL"))
    )
    (comp (ref "U$190")
      (value "ELECTRODE60MIL")
      (footprint "eagle-import:61MIL")
      (libsource (lib "eagle-import") (part "ELECTRODE60MIL"))
    )
    (comp (ref "U$191")
      (value "ELECTRODE60MIL")
      (footprint "eagle-import:61MIL")
      (libsource (lib "eagle-import") (part "ELECTRODE60MIL"))
    )
    (comp (ref "U$192")
      (value "ELECTRODE60MIL")
      (footprint "eagle-import:61MIL")
      (libsource (lib "eagle-import") (part "ELECTRODE60MIL"))
    )
    (comp (ref "U$193")
      (value "ELECTRODE60MIL")
      (footprint "eagle-import:61MIL")
      (libsource (lib "eagle-import") (part "ELECTRODE60MIL"))
    )
    (comp (ref "U$194")
      (value "ELECTRODE60MIL")
      (footprint "eagle-import:61MIL")
      (libsource (lib "eagle-import") (part "ELECTRODE60MIL"))
    )
    (comp (ref "U$195")
      (value "ELECTRODE60MIL")
      (footprint "eagle-import:61MIL")
      (libsource (lib "eagle-import") (part "ELECTRODE60MIL"))
    )
    (comp (ref "U$196")
      (value "ELECTRODE61MILJCT")
      (footprint "eagle-import:61MILJCT")
      (libsource (lib "eagle-import") (part "ELECTRODE61MILJCT"))
    )
    (comp (ref "U$197")
      (value "ELECTRODE60MIL")
      (footprint "eagle-import:61MIL")
      (libsource (lib "eagle-import") (part "ELECTRODE60MIL"))
    )
    (comp (ref "U$198")
      (value "ELECTRODE60MIL")
      (footprint "eagle-import:61MIL")
      (libsource (lib "eagle-import") (part "ELECTRODE60MIL"))
    )
    (comp (ref "U$199")
      (value "ELECTRODE60MIL")
      (footprint "eagle-import:61MIL")
      (libsource (lib "eagle-import") (part "ELECTRODE60MIL"))
    )
    (comp (ref "U$200")
      (value "ELECTRODE60MIL")
      (footprint "eagle-import:61MIL")
      (libsource (lib "eagle-import") (part "ELECTRODE60MIL"))
    )
    (comp (ref "U$201")
      (value "ELECTRODE60MIL")
      (footprint "eagle-import:61MIL")
      (libsource (lib "eagle-import") (part "ELECTRODE60MIL"))
    )
    (comp (ref "U$202")
      (value "ELECTRODE60MIL")
      (footprint "eagle-import:61MIL")
      (libsource (lib "eagle-import") (part "ELECTRODE60MIL"))
    )
    (comp (ref "U$203")
      (value "ELECTRODE60MIL")
      (footprint "eagle-import:61MIL")
      (libsource (lib "eagle-import") (part "ELECTRODE60MIL"))
    )
    (comp (ref "U$204")
      (value "ELECTRODE60MIL")
      (footprint "eagle-import:61MIL")
      (libsource (lib "eagle-import") (part "ELECTRODE60MIL"))
    )
    (comp (ref "U$205")
      (value "ELECTRODE60MIL")
      (footprint "eagle-import:61MIL")
      (libsource (lib "eagle-import") (part "ELECTRODE60MIL"))
    )
    (comp (ref "U$206")
      (value "ELECTRODE60MIL")
      (footprint "eagle-import:61MIL")
      (libsource (lib "eagle-import") (part "ELECTRODE60MIL"))
    )
    (comp (ref "U$207")
      (value "ELECTRODE60MIL")
      (footprint "eagle-import:61MIL")
      (libsource (lib "eagle-import") (part "ELECTRODE60MIL"))
    )
    (comp (ref "U$208")
      (value "ELECTRODE60MIL")
      (footprint "eagle-import:61MIL")
      (libsource (lib "eagle-import") (part "ELECTRODE60MIL"))
    )
    (comp (ref "U$209")
      (value "ELECTRODE60MIL")
      (footprint "eagle-import:61MIL")
      (libsource (lib "eagle-import") (part "ELECTRODE60MIL"))
    )
    (comp (ref "U$210")
      (value "ELECTRODE60MIL")
      (footprint "eagle-import:61MIL")
      (libsource (lib "eagle-import") (part "ELECTRODE60MIL"))
    )
    (comp (ref "U$211")
      (value "ELECTRODE61MILJCT")
      (footprint "eagle-import:61MILJCT")
      (libsource (lib "eagle-import") (part "ELECTRODE61MILJCT"))
    )
    (comp (ref "U$212")
      (value "ELECTRODE60MIL")
      (footprint "eagle-import:61MIL")
      (libsource (lib "eagle-import") (part "ELECTRODE60MIL"))
    )
    (comp (ref "U$213")
      (value "ELECTRODE60MIL")
      (footprint "eagle-import:61MIL")
      (libsource (lib "eagle-import") (part "ELECTRODE60MIL"))
    )
    (comp (ref "U$214")
      (value "ELECTRODE60MIL")
      (footprint "eagle-import:61MIL")
      (libsource (lib "eagle-import") (part "ELECTRODE60MIL"))
    )
    (comp (ref "U$215")
      (value "ELECTRODE60MIL")
      (footprint "eagle-import:61MIL")
      (libsource (lib "eagle-import") (part "ELECTRODE60MIL"))
    )
    (comp (ref "U$216")
      (value "ELECTRODE60MIL")
      (footprint "eagle-import:61MIL")
      (libsource (lib "eagle-import") (part "ELECTRODE60MIL"))
    )
    (comp (ref "U$217")
      (value "ELECTRODE60MIL")
      (footprint "eagle-import:61MIL")
      (libsource (lib "eagle-import") (part "ELECTRODE60MIL"))
    )
    (comp (ref "U$218")
      (value "ELECTRODE60MIL")
      (footprint "eagle-import:61MIL")
      (libsource (lib "eagle-import") (part "ELECTRODE60MIL"))
    )
    (comp (ref "U$219")
      (value "ELECTRODE60MIL")
      (footprint "eagle-import:61MIL")
      (libsource (lib "eagle-import") (part "ELECTRODE60MIL"))
    )
    (comp (ref "U$220")
      (value "ELECTRODE60MIL")
      (footprint "eagle-import:61MIL")
      (libsource (lib "eagle-import") (part "ELECTRODE60MIL"))
    )
    (comp (ref "U$221")
      (value "ELECTRODE60MIL")
      (footprint "eagle-import:61MIL")
      (libsource (lib "eagle-import") (part "ELECTRODE60MIL"))
    )
    (comp (ref "U$222")
      (value "ELECTRODE60MIL")
      (footprint "eagle-import:61MIL")
      (libsource (lib "eagle-import") (part "ELECTRODE60MIL"))
    )
    (comp (ref "U$223")
      (value "ELECTRODE60MIL")
      (footprint "eagle-import:61MIL")
      (libsource (lib "eagle-import") (part "ELECTRODE60MIL"))
    )
    (comp (ref "U$224")
      (value "ELECTRODE60MIL")
      (footprint "eagle-import:61MIL")
      (libsource (lib "eagle-import") (part "ELECTRODE60MIL"))
    )
    (comp (ref "U$225")
      (value "ELECTRODE60MIL")
      (footprint "eagle-import:61MIL")
      (libsource (lib "eagle-import") (part "ELECTRODE60MIL"))
    )
    (comp (ref "U$226")
      (value "ELECTRODE61MILJCT")
      (footprint "eagle-import:61MILJCT")
      (libsource (lib "eagle-import") (part "ELECTRODE61MILJCT"))
    )
    (comp (ref "U$227")
      (value "ELECTRODE60MIL")
      (footprint "eagle-import:61MIL")
      (libsource (lib "eagle-import") (part "ELECTRODE60MIL"))
    )
    (comp (ref "U$228")
      (value "ELECTRODE60MIL")
      (footprint "eagle-import:61MIL")
      (libsource (lib "eagle-import") (part "ELECTRODE60MIL"))
    )
    (comp (ref "U$229")
      (value "ELECTRODE60MIL")
      (footprint "eagle-import:61MIL")
      (libsource (lib "eagle-import") (part "ELECTRODE60MIL"))
    )
    (comp (ref "U$230")
      (value "ELECTRODE60MIL")
      (footprint "eagle-import:61MIL")
      (libsource (lib "eagle-import") (part "ELECTRODE60MIL"))
    )
    (comp (ref "U$231")
      (value "ELECTRODE60MIL")
      (footprint "eagle-import:61MIL")
      (libsource (lib "eagle-import") (part "ELECTRODE60MIL"))
    )
    (comp (ref "U$232")
      (value "ELECTRODE60MIL")
      (footprint "eagle-import:61MIL")
      (libsource (lib "eagle-import") (part "ELECTRODE60MIL"))
    )
    (comp (ref "U$233")
      (value "ELECTRODE60MIL")
      (footprint "eagle-import:61MIL")
      (libsource (lib "eagle-import") (part "ELECTRODE60MIL"))
    )
    (comp (ref "U$234")
      (value "ELECTRODE60MIL")
      (footprint "eagle-import:61MIL")
      (libsource (lib "eagle-import") (part "ELECTRODE60MIL"))
    )
    (comp (ref "U$235")
      (value "ELECTRODE60MIL")
      (footprint "eagle-import:61MIL")
      (libsource (lib "eagle-import") (part "ELECTRODE60MIL"))
    )
    (comp (ref "U$236")
      (value "ELECTRODE60MIL")
      (footprint "eagle-import:61MIL")
      (libsource (lib "eagle-import") (part "ELECTRODE60MIL"))
    )
    (comp (ref "U$237")
      (value "ELECTRODE60MIL")
      (footprint "eagle-import:61MIL")
      (libsource (lib "eagle-import") (part "ELECTRODE60MIL"))
    )
    (comp (ref "U$238")
      (value "ELECTRODE60MIL")
      (footprint "eagle-import:61MIL")
      (libsource (lib "eagle-import") (part "ELECTRODE60MIL"))
    )
    (comp (ref "U$239")
      (value "ELECTRODE60MIL")
      (footprint "eagle-import:61MIL")
      (libsource (lib "eagle-import") (part "ELECTRODE60MIL"))
    )
    (comp (ref "U$240")
      (value "ELECTRODE60MIL")
      (footprint "eagle-import:61MIL")
      (libsource (lib "eagle-import") (part "ELECTRODE60MIL"))
    )
    (comp (ref "U$241")
      (value "ELECTRODE61MILJCT")
      (footprint "eagle-import:61MILJCT")
      (libsource (lib "eagle-import") (part "ELECTRODE61MILJCT"))
    )
    (comp (ref "U$242")
      (value "ELECTRODE60MIL")
      (footprint "eagle-import:61MIL")
      (libsource (lib "eagle-import") (part "ELECTRODE60MIL"))
    )
    (comp (ref "U$243")
      (value "ELECTRODE60MIL")
      (footprint "eagle-import:61MIL")
      (libsource (lib "eagle-import") (part "ELECTRODE60MIL"))
    )
    (comp (ref "U$244")
      (value "ELECTRODE60MIL")
      (footprint "eagle-import:61MIL")
      (libsource (lib "eagle-import") (part "ELECTRODE60MIL"))
    )
    (comp (ref "U$245")
      (value "ELECTRODE60MIL")
      (footprint "eagle-import:61MIL")
      (libsource (lib "eagle-import") (part "ELECTRODE60MIL"))
    )
    (comp (ref "U$246")
      (value "ELECTRODE60MIL")
      (footprint "eagle-import:61MIL")
      (libsource (lib "eagle-import") (part "ELECTRODE60MIL"))
    )
    (comp (ref "U$247")
      (value "ELECTRODE60MIL")
      (footprint "eagle-import:61MIL")
      (libsource (lib "eagle-import") (part "ELECTRODE60MIL"))
    )
    (comp (ref "U$248")
      (value "ELECTRODE60MIL")
      (footprint "eagle-import:61MIL")
      (libsource (lib "eagle-import") (part "ELECTRODE60MIL"))
    )
    (comp (ref "U$249")
      (value "ELECTRODE60MIL")
      (footprint "eagle-import:61MIL")
      (libsource (lib "eagle-import") (part "ELECTRODE60MIL"))
    )
    (comp (ref "U$250")
      (value "ELECTRODE60MIL")
      (footprint "eagle-import:61MIL")
      (libsource (lib "eagle-import") (part "ELECTRODE60MIL"))
    )
    (comp (ref "U$251")
      (value "ELECTRODE60MIL")
      (footprint "eagle-import:61MIL")
      (libsource (lib "eagle-import") (part "ELECTRODE60MIL"))
    )
    (comp (ref "U$252")
      (value "ELECTRODE60MIL")
      (footprint "eagle-import:61MIL")
      (libsource (lib "eagle-import") (part "ELECTRODE60MIL"))
    )
    (comp (ref "U$253")
      (value "ELECTRODE60MIL")
      (footprint "eagle-import:61MIL")
      (libsource (lib "eagle-import") (part "ELECTRODE60MIL"))
    )
    (comp (ref "U$254")
      (value "ELECTRODE60MIL")
      (footprint "eagle-import:61MIL")
      (libsource (lib "eagle-import") (part "ELECTRODE60MIL"))
    )
    (comp (ref "U$255")
      (value "ELECTRODE60MIL")
      (footprint "eagle-import:61MIL")
      (libsource (lib "eagle-import") (part "ELECTRODE60MIL"))
    )
    (comp (ref "U$256")
      (value "ELECTRODE60MIL")
      (footprint "eagle-import:61MIL")
      (libsource (lib "eagle-import") (part "ELECTRODE60MIL"))
    )
    (comp (ref "U$257")
      (value "FPC-0.5-32")
      (footprint "eagle-import:FPC-32-WIRE")
      (libsource (lib "eagle-import") (part "FPC-0.5-32"))
    )
  )
  (nets
    (net (code "1") (name "Net-(U$257-1)") (class "Default")
      (node (ref "U$241") (pin "-") (pinfunction "-_-") (pintype "bidirectional"))
      (node (ref "U$242") (pin "-") (pinfunction "-_-") (pintype "bidirectional"))
      (node (ref "U$243") (pin "-") (pinfunction "-_-") (pintype "bidirectional"))
      (node (ref "U$244") (pin "-") (pinfunction "-_-") (pintype "bidirectional"))
      (node (ref "U$245") (pin "-") (pinfunction "-_-") (pintype "bidirectional"))
      (node (ref "U$246") (pin "-") (pinfunction "-_-") (pintype "bidirectional"))
      (node (ref "U$247") (pin "-") (pinfunction "-_-") (pintype "bidirectional"))
      (node (ref "U$248") (pin "-") (pinfunction "-_-") (pintype "bidirectional"))
      (node (ref "U$249") (pin "-") (pinfunction "-_-") (pintype "bidirectional"))
      (node (ref "U$250") (pin "-") (pinfunction "-_-") (pintype "bidirectional"))
      (node (ref "U$251") (pin "-") (pinfunction "-_-") (pintype "bidirectional"))
      (node (ref "U$252") (pin "-") (pinfunction "-_-") (pintype "bidirectional"))
      (node (ref "U$253") (pin "-") (pinfunction "-_-") (pintype "bidirectional"))
      (node (ref "U$254") (pin "-") (pinfunction "-_-") (pintype "bidirectional"))
      (node (ref "U$255") (pin "-") (pinfunction "-_-") (pintype "bidirectional"))
      (node (ref "U$256") (pin "-") (pinfunction "-_-") (pintype "bidirectional"))
      (node (ref "U$257") (pin "P$1") (pinfunction "1_P$1") (pintype "bidirectional"))
    )
    (net (code "2") (name "Net-(U$257-2)") (class "Default")
      (node (ref "U$1") (pin "+") (pinfunction "+_+") (pintype "bidirectional"))
      (node (ref "U$113") (pin "+") (pinfunction "+_+") (pintype "bidirectional"))
      (node (ref "U$129") (pin "+") (pinfunction "+_+") (pintype "bidirectional"))
      (node (ref "U$145") (pin "+") (pinfunction "+_+") (pintype "bidirectional"))
      (node (ref "U$161") (pin "+") (pinfunction "+_+") (pintype "bidirectional"))
      (node (ref "U$17") (pin "+") (pinfunction "+_+") (pintype "bidirectional"))
      (node (ref "U$177") (pin "+") (pinfunction "+_+") (pintype "bidirectional"))
      (node (ref "U$193") (pin "+") (pinfunction "+_+") (pintype "bidirectional"))
      (node (ref "U$209") (pin "+") (pinfunction "+_+") (pintype "bidirectional"))
      (node (ref "U$225") (pin "+") (pinfunction "+_+") (pintype "bidirectional"))
      (node (ref "U$241") (pin "+") (pinfunction "+_+") (pintype "bidirectional"))
      (node (ref "U$257") (pin "P$2") (pinfunction "2_P$2") (pintype "bidirectional"))
      (node (ref "U$33") (pin "+") (pinfunction "+_+") (pintype "bidirectional"))
      (node (ref "U$49") (pin "+") (pinfunction "+_+") (pintype "bidirectional"))
      (node (ref "U$65") (pin "+") (pinfunction "+_+") (pintype "bidirectional"))
      (node (ref "U$81") (pin "+") (pinfunction "+_+") (pintype "bidirectional"))
      (node (ref "U$97") (pin "+") (pinfunction "+_+") (pintype "bidirectional"))
    )
    (net (code "3") (name "Net-(U$257-3)") (class "Default")
      (node (ref "U$225") (pin "-") (pinfunction "-_-") (pintype "bidirectional"))
      (node (ref "U$226") (pin "-") (pinfunction "-_-") (pintype "bidirectional"))
      (node (ref "U$227") (pin "-") (pinfunction "-_-") (pintype "bidirectional"))
      (node (ref "U$228") (pin "-") (pinfunction "-_-") (pintype "bidirectional"))
      (node (ref "U$229") (pin "-") (pinfunction "-_-") (pintype "bidirectional"))
      (node (ref "U$230") (pin "-") (pinfunction "-_-") (pintype "bidirectional"))
      (node (ref "U$231") (pin "-") (pinfunction "-_-") (pintype "bidirectional"))
      (node (ref "U$232") (pin "-") (pinfunction "-_-") (pintype "bidirectional"))
      (node (ref "U$233") (pin "-") (pinfunction "-_-") (pintype "bidirectional"))
      (node (ref "U$234") (pin "-") (pinfunction "-_-") (pintype "bidirectional"))
      (node (ref "U$235") (pin "-") (pinfunction "-_-") (pintype "bidirectional"))
      (node (ref "U$236") (pin "-") (pinfunction "-_-") (pintype "bidirectional"))
      (node (ref "U$237") (pin "-") (pinfunction "-_-") (pintype "bidirectional"))
      (node (ref "U$238") (pin "-") (pinfunction "-_-") (pintype "bidirectional"))
      (node (ref "U$239") (pin "-") (pinfunction "-_-") (pintype "bidirectional"))
      (node (ref "U$240") (pin "-") (pinfunction "-_-") (pintype "bidirectional"))
      (node (ref "U$257") (pin "P$3") (pinfunction "3_P$3") (pintype "bidirectional"))
    )
    (net (code "4") (name "Net-(U$257-4)") (class "Default")
      (node (ref "U$114") (pin "+") (pinfunction "+_+") (pintype "bidirectional"))
      (node (ref "U$130") (pin "+") (pinfunction "+_+") (pintype "bidirectional"))
      (node (ref "U$146") (pin "+") (pinfunction "+_+") (pintype "bidirectional"))
      (node (ref "U$162") (pin "+") (pinfunction "+_+") (pintype "bidirectional"))
      (node (ref "U$178") (pin "+") (pinfunction "+_+") (pintype "bidirectional"))
      (node (ref "U$18") (pin "+") (pinfunction "+_+") (pintype "bidirectional"))
      (node (ref "U$194") (pin "+") (pinfunction "+_+") (pintype "bidirectional"))
      (node (ref "U$2") (pin "+") (pinfunction "+_+") (pintype "bidirectional"))
      (node (ref "U$210") (pin "+") (pinfunction "+_+") (pintype "bidirectional"))
      (node (ref "U$226") (pin "+") (pinfunction "+_+") (pintype "bidirectional"))
      (node (ref "U$242") (pin "+") (pinfunction "+_+") (pintype "bidirectional"))
      (node (ref "U$257") (pin "P$4") (pinfunction "4_P$4") (pintype "bidirectional"))
      (node (ref "U$34") (pin "+") (pinfunction "+_+") (pintype "bidirectional"))
      (node (ref "U$50") (pin "+") (pinfunction "+_+") (pintype "bidirectional"))
      (node (ref "U$66") (pin "+") (pinfunction "+_+") (pintype "bidirectional"))
      (node (ref "U$82") (pin "+") (pinfunction "+_+") (pintype "bidirectional"))
      (node (ref "U$98") (pin "+") (pinfunction "+_+") (pintype "bidirectional"))
    )
    (net (code "5") (name "Net-(U$257-5)") (class "Default")
      (node (ref "U$209") (pin "-") (pinfunction "-_-") (pintype "bidirectional"))
      (node (ref "U$210") (pin "-") (pinfunction "-_-") (pintype "bidirectional"))
      (node (ref "U$211") (pin "-") (pinfunction "-_-") (pintype "bidirectional"))
      (node (ref "U$212") (pin "-") (pinfunction "-_-") (pintype "bidirectional"))
      (node (ref "U$213") (pin "-") (pinfunction "-_-") (pintype "bidirectional"))
      (node (ref "U$214") (pin "-") (pinfunction "-_-") (pintype "bidirectional"))
      (node (ref "U$215") (pin "-") (pinfunction "-_-") (pintype "bidirectional"))
      (node (ref "U$216") (pin "-") (pinfunction "-_-") (pintype "bidirectional"))
      (node (ref "U$217") (pin "-") (pinfunction "-_-") (pintype "bidirectional"))
      (node (ref "U$218") (pin "-") (pinfunction "-_-") (pintype "bidirectional"))
      (node (ref "U$219") (pin "-") (pinfunction "-_-") (pintype "bidirectional"))
      (node (ref "U$220") (pin "-") (pinfunction "-_-") (pintype "bidirectional"))
      (node (ref "U$221") (pin "-") (pinfunction "-_-") (pintype "bidirectional"))
      (node (ref "U$222") (pin "-") (pinfunction "-_-") (pintype "bidirectional"))
      (node (ref "U$223") (pin "-") (pinfunction "-_-") (pintype "bidirectional"))
      (node (ref "U$224") (pin "-") (pinfunction "-_-") (pintype "bidirectional"))
      (node (ref "U$257") (pin "P$5") (pinfunction "5_P$5") (pintype "bidirectional"))
    )
    (net (code "6") (name "Net-(U$257-6)") (class "Default")
      (node (ref "U$115") (pin "+") (pinfunction "+_+") (pintype "bidirectional"))
      (node (ref "U$131") (pin "+") (pinfunction "+_+") (pintype "bidirectional"))
      (node (ref "U$147") (pin "+") (pinfunction "+_+") (pintype "bidirectional"))
      (node (ref "U$163") (pin "+") (pinfunction "+_+") (pintype "bidirectional"))
      (node (ref "U$179") (pin "+") (pinfunction "+_+") (pintype "bidirectional"))
      (node (ref "U$19") (pin "+") (pinfunction "+_+") (pintype "bidirectional"))
      (node (ref "U$195") (pin "+") (pinfunction "+_+") (pintype "bidirectional"))
      (node (ref "U$211") (pin "+") (pinfunction "+_+") (pintype "bidirectional"))
      (node (ref "U$227") (pin "+") (pinfunction "+_+") (pintype "bidirectional"))
      (node (ref "U$243") (pin "+") (pinfunction "+_+") (pintype "bidirectional"))
      (node (ref "U$257") (pin "P$6") (pinfunction "6_P$6") (pintype "bidirectional"))
      (node (ref "U$3") (pin "+") (pinfunction "+_+") (pintype "bidirectional"))
      (node (ref "U$35") (pin "+") (pinfunction "+_+") (pintype "bidirectional"))
      (node (ref "U$51") (pin "+") (pinfunction "+_+") (pintype "bidirectional"))
      (node (ref "U$67") (pin "+") (pinfunction "+_+") (pintype "bidirectional"))
      (node (ref "U$83") (pin "+") (pinfunction "+_+") (pintype "bidirectional"))
      (node (ref "U$99") (pin "+") (pinfunction "+_+") (pintype "bidirectional"))
    )
    (net (code "7") (name "Net-(U$257-7)") (class "Default")
      (node (ref "U$193") (pin "-") (pinfunction "-_-") (pintype "bidirectional"))
      (node (ref "U$194") (pin "-") (pinfunction "-_-") (pintype "bidirectional"))
      (node (ref "U$195") (pin "-") (pinfunction "-_-") (pintype "bidirectional"))
      (node (ref "U$196") (pin "-") (pinfunction "-_-") (pintype "bidirectional"))
      (node (ref "U$197") (pin "-") (pinfunction "-_-") (pintype "bidirectional"))
      (node (ref "U$198") (pin "-") (pinfunction "-_-") (pintype "bidirectional"))
      (node (ref "U$199") (pin "-") (pinfunction "-_-") (pintype "bidirectional"))
      (node (ref "U$200") (pin "-") (pinfunction "-_-") (pintype "bidirectional"))
      (node (ref "U$201") (pin "-") (pinfunction "-_-") (pintype "bidirectional"))
      (node (ref "U$202") (pin "-") (pinfunction "-_-") (pintype "bidirectional"))
      (node (ref "U$203") (pin "-") (pinfunction "-_-") (pintype "bidirectional"))
      (node (ref "U$204") (pin "-") (pinfunction "-_-") (pintype "bidirectional"))
      (node (ref "U$205") (pin "-") (pinfunction "-_-") (pintype "bidirectional"))
      (node (ref "U$206") (pin "-") (pinfunction "-_-") (pintype "bidirectional"))
      (node (ref "U$207") (pin "-") (pinfunction "-_-") (pintype "bidirectional"))
      (node (ref "U$208") (pin "-") (pinfunction "-_-") (pintype "bidirectional"))
      (node (ref "U$257") (pin "P$7") (pinfunction "7_P$7") (pintype "bidirectional"))
    )
    (net (code "8") (name "Net-(U$257-8)") (class "Default")
      (node (ref "U$100") (pin "+") (pinfunction "+_+") (pintype "bidirectional"))
      (node (ref "U$116") (pin "+") (pinfunction "+_+") (pintype "bidirectional"))
      (node (ref "U$132") (pin "+") (pinfunction "+_+") (pintype "bidirectional"))
      (node (ref "U$148") (pin "+") (pinfunction "+_+") (pintype "bidirectional"))
      (node (ref "U$164") (pin "+") (pinfunction "+_+") (pintype "bidirectional"))
      (node (ref "U$180") (pin "+") (pinfunction "+_+") (pintype "bidirectional"))
      (node (ref "U$196") (pin "+") (pinfunction "+_+") (pintype "bidirectional"))
      (node (ref "U$20") (pin "+") (pinfunction "+_+") (pintype "bidirectional"))
      (node (ref "U$212") (pin "+") (pinfunction "+_+") (pintype "bidirectional"))
      (node (ref "U$228") (pin "+") (pinfunction "+_+") (pintype "bidirectional"))
      (node (ref "U$244") (pin "+") (pinfunction "+_+") (pintype "bidirectional"))
      (node (ref "U$257") (pin "P$8") (pinfunction "8_P$8") (pintype "bidirectional"))
      (node (ref "U$36") (pin "+") (pinfunction "+_+") (pintype "bidirectional"))
      (node (ref "U$4") (pin "+") (pinfunction "+_+") (pintype "bidirectional"))
      (node (ref "U$52") (pin "+") (pinfunction "+_+") (pintype "bidirectional"))
      (node (ref "U$68") (pin "+") (pinfunction "+_+") (pintype "bidirectional"))
      (node (ref "U$84") (pin "+") (pinfunction "+_+") (pintype "bidirectional"))
    )
    (net (code "9") (name "Net-(U$257-9)") (class "Default")
      (node (ref "U$177") (pin "-") (pinfunction "-_-") (pintype "bidirectional"))
      (node (ref "U$178") (pin "-") (pinfunction "-_-") (pintype "bidirectional"))
      (node (ref "U$179") (pin "-") (pinfunction "-_-") (pintype "bidirectional"))
      (node (ref "U$180") (pin "-") (pinfunction "-_-") (pintype "bidirectional"))
      (node (ref "U$181") (pin "-") (pinfunction "-_-") (pintype "bidirectional"))
      (node (ref "U$182") (pin "-") (pinfunction "-_-") (pintype "bidirectional"))
      (node (ref "U$183") (pin "-") (pinfunction "-_-") (pintype "bidirectional"))
      (node (ref "U$184") (pin "-") (pinfunction "-_-") (pintype "bidirectional"))
      (node (ref "U$185") (pin "-") (pinfunction "-_-") (pintype "bidirectional"))
      (node (ref "U$186") (pin "-") (pinfunction "-_-") (pintype "bidirectional"))
      (node (ref "U$187") (pin "-") (pinfunction "-_-") (pintype "bidirectional"))
      (node (ref "U$188") (pin "-") (pinfunction "-_-") (pintype "bidirectional"))
      (node (ref "U$189") (pin "-") (pinfunction "-_-") (pintype "bidirectional"))
      (node (ref "U$190") (pin "-") (pinfunction "-_-") (pintype "bidirectional"))
      (node (ref "U$191") (pin "-") (pinfunction "-_-") (pintype "bidirectional"))
      (node (ref "U$192") (pin "-") (pinfunction "-_-") (pintype "bidirectional"))
      (node (ref "U$257") (pin "P$9") (pinfunction "9_P$9") (pintype "bidirectional"))
    )
    (net (code "10") (name "Net-(U$257-10)") (class "Default")
      (node (ref "U$101") (pin "+") (pinfunction "+_+") (pintype "bidirectional"))
      (node (ref "U$117") (pin "+") (pinfunction "+_+") (pintype "bidirectional"))
      (node (ref "U$133") (pin "+") (pinfunction "+_+") (pintype "bidirectional"))
      (node (ref "U$149") (pin "+") (pinfunction "+_+") (pintype "bidirectional"))
      (node (ref "U$165") (pin "+") (pinfunction "+_+") (pintype "bidirectional"))
      (node (ref "U$181") (pin "+") (pinfunction "+_+") (pintype "bidirectional"))
      (node (ref "U$197") (pin "+") (pinfunction "+_+") (pintype "bidirectional"))
      (node (ref "U$21") (pin "+") (pinfunction "+_+") (pintype "bidirectional"))
      (node (ref "U$213") (pin "+") (pinfunction "+_+") (pintype "bidirectional"))
      (node (ref "U$229") (pin "+") (pinfunction "+_+") (pintype "bidirectional"))
      (node (ref "U$245") (pin "+") (pinfunction "+_+") (pintype "bidirectional"))
      (node (ref "U$257") (pin "P$10") (pinfunction "10_P$10") (pintype "bidirectional"))
      (node (ref "U$37") (pin "+") (pinfunction "+_+") (pintype "bidirectional"))
      (node (ref "U$5") (pin "+") (pinfunction "+_+") (pintype "bidirectional"))
      (node (ref "U$53") (pin "+") (pinfunction "+_+") (pintype "bidirectional"))
      (node (ref "U$69") (pin "+") (pinfunction "+_+") (pintype "bidirectional"))
      (node (ref "U$85") (pin "+") (pinfunction "+_+") (pintype "bidirectional"))
    )
    (net (code "11") (name "Net-(U$257-11)") (class "Default")
      (node (ref "U$161") (pin "-") (pinfunction "-_-") (pintype "bidirectional"))
      (node (ref "U$162") (pin "-") (pinfunction "-_-") (pintype "bidirectional"))
      (node (ref "U$163") (pin "-") (pinfunction "-_-") (pintype "bidirectional"))
      (node (ref "U$164") (pin "-") (pinfunction "-_-") (pintype "bidirectional"))
      (node (ref "U$165") (pin "-") (pinfunction "-_-") (pintype "bidirectional"))
      (node (ref "U$166") (pin "-") (pinfunction "-_-") (pintype "bidirectional"))
      (node (ref "U$167") (pin "-") (pinfunction "-_-") (pintype "bidirectional"))
      (node (ref "U$168") (pin "-") (pinfunction "-_-") (pintype "bidirectional"))
      (node (ref "U$169") (pin "-") (pinfunction "-_-") (pintype "bidirectional"))
      (node (ref "U$170") (pin "-") (pinfunction "-_-") (pintype "bidirectional"))
      (node (ref "U$171") (pin "-") (pinfunction "-_-") (pintype "bidirectional"))
      (node (ref "U$172") (pin "-") (pinfunction "-_-") (pintype "bidirectional"))
      (node (ref "U$173") (pin "-") (pinfunction "-_-") (pintype "bidirectional"))
      (node (ref "U$174") (pin "-") (pinfunction "-_-") (pintype "bidirectional"))
      (node (ref "U$175") (pin "-") (pinfunction "-_-") (pintype "bidirectional"))
      (node (ref "U$176") (pin "-") (pinfunction "-_-") (pintype "bidirectional"))
      (node (ref "U$257") (pin "P$11") (pinfunction "11_P$11") (pintype "bidirectional"))
    )
    (net (code "12") (name "Net-(U$257-12)") (class "Default")
      (node (ref "U$102") (pin "+") (pinfunction "+_+") (pintype "bidirectional"))
      (node (ref "U$118") (pin "+") (pinfunction "+_+") (pintype "bidirectional"))
      (node (ref "U$134") (pin "+") (pinfunction "+_+") (pintype "bidirectional"))
      (node (ref "U$150") (pin "+") (pinfunction "+_+") (pintype "bidirectional"))
      (node (ref "U$166") (pin "+") (pinfunction "+_+") (pintype "bidirectional"))
      (node (ref "U$182") (pin "+") (pinfunction "+_+") (pintype "bidirectional"))
      (node (ref "U$198") (pin "+") (pinfunction "+_+") (pintype "bidirectional"))
      (node (ref "U$214") (pin "+") (pinfunction "+_+") (pintype "bidirectional"))
      (node (ref "U$22") (pin "+") (pinfunction "+_+") (pintype "bidirectional"))
      (node (ref "U$230") (pin "+") (pinfunction "+_+") (pintype "bidirectional"))
      (node (ref "U$246") (pin "+") (pinfunction "+_+") (pintype "bidirectional"))
      (node (ref "U$257") (pin "P$12") (pinfunction "12_P$12") (pintype "bidirectional"))
      (node (ref "U$38") (pin "+") (pinfunction "+_+") (pintype "bidirectional"))
      (node (ref "U$54") (pin "+") (pinfunction "+_+") (pintype "bidirectional"))
      (node (ref "U$6") (pin "+") (pinfunction "+_+") (pintype "bidirectional"))
      (node (ref "U$70") (pin "+") (pinfunction "+_+") (pintype "bidirectional"))
      (node (ref "U$86") (pin "+") (pinfunction "+_+") (pintype "bidirectional"))
    )
    (net (code "13") (name "Net-(U$257-13)") (class "Default")
      (node (ref "U$145") (pin "-") (pinfunction "-_-") (pintype "bidirectional"))
      (node (ref "U$146") (pin "-") (pinfunction "-_-") (pintype "bidirectional"))
      (node (ref "U$147") (pin "-") (pinfunction "-_-") (pintype "bidirectional"))
      (node (ref "U$148") (pin "-") (pinfunction "-_-") (pintype "bidirectional"))
      (node (ref "U$149") (pin "-") (pinfunction "-_-") (pintype "bidirectional"))
      (node (ref "U$150") (pin "-") (pinfunction "-_-") (pintype "bidirectional"))
      (node (ref "U$151") (pin "-") (pinfunction "-_-") (pintype "bidirectional"))
      (node (ref "U$152") (pin "-") (pinfunction "-_-") (pintype "bidirectional"))
      (node (ref "U$153") (pin "-") (pinfunction "-_-") (pintype "bidirectional"))
      (node (ref "U$154") (pin "-") (pinfunction "-_-") (pintype "bidirectional"))
      (node (ref "U$155") (pin "-") (pinfunction "-_-") (pintype "bidirectional"))
      (node (ref "U$156") (pin "-") (pinfunction "-_-") (pintype "bidirectional"))
      (node (ref "U$157") (pin "-") (pinfunction "-_-") (pintype "bidirectional"))
      (node (ref "U$158") (pin "-") (pinfunction "-_-") (pintype "bidirectional"))
      (node (ref "U$159") (pin "-") (pinfunction "-_-") (pintype "bidirectional"))
      (node (ref "U$160") (pin "-") (pinfunction "-_-") (pintype "bidirectional"))
      (node (ref "U$257") (pin "P$13") (pinfunction "13_P$13") (pintype "bidirectional"))
    )
    (net (code "14") (name "Net-(U$257-14)") (class "Default")
      (node (ref "U$103") (pin "+") (pinfunction "+_+") (pintype "bidirectional"))
      (node (ref "U$119") (pin "+") (pinfunction "+_+") (pintype "bidirectional"))
      (node (ref "U$135") (pin "+") (pinfunction "+_+") (pintype "bidirectional"))
      (node (ref "U$151") (pin "+") (pinfunction "+_+") (pintype "bidirectional"))
      (node (ref "U$167") (pin "+") (pinfunction "+_+") (pintype "bidirectional"))
      (node (ref "U$183") (pin "+") (pinfunction "+_+") (pintype "bidirectional"))
      (node (ref "U$199") (pin "+") (pinfunction "+_+") (pintype "bidirectional"))
      (node (ref "U$215") (pin "+") (pinfunction "+_+") (pintype "bidirectional"))
      (node (ref "U$23") (pin "+") (pinfunction "+_+") (pintype "bidirectional"))
      (node (ref "U$231") (pin "+") (pinfunction "+_+") (pintype "bidirectional"))
      (node (ref "U$247") (pin "+") (pinfunction "+_+") (pintype "bidirectional"))
      (node (ref "U$257") (pin "P$14") (pinfunction "14_P$14") (pintype "bidirectional"))
      (node (ref "U$39") (pin "+") (pinfunction "+_+") (pintype "bidirectional"))
      (node (ref "U$55") (pin "+") (pinfunction "+_+") (pintype "bidirectional"))
      (node (ref "U$7") (pin "+") (pinfunction "+_+") (pintype "bidirectional"))
      (node (ref "U$71") (pin "+") (pinfunction "+_+") (pintype "bidirectional"))
      (node (ref "U$87") (pin "+") (pinfunction "+_+") (pintype "bidirectional"))
    )
    (net (code "15") (name "Net-(U$257-15)") (class "Default")
      (node (ref "U$129") (pin "-") (pinfunction "-_-") (pintype "bidirectional"))
      (node (ref "U$130") (pin "-") (pinfunction "-_-") (pintype "bidirectional"))
      (node (ref "U$131") (pin "-") (pinfunction "-_-") (pintype "bidirectional"))
      (node (ref "U$132") (pin "-") (pinfunction "-_-") (pintype "bidirectional"))
      (node (ref "U$133") (pin "-") (pinfunction "-_-") (pintype "bidirectional"))
      (node (ref "U$134") (pin "-") (pinfunction "-_-") (pintype "bidirectional"))
      (node (ref "U$135") (pin "-") (pinfunction "-_-") (pintype "bidirectional"))
      (node (ref "U$136") (pin "-") (pinfunction "-_-") (pintype "bidirectional"))
      (node (ref "U$137") (pin "-") (pinfunction "-_-") (pintype "bidirectional"))
      (node (ref "U$138") (pin "-") (pinfunction "-_-") (pintype "bidirectional"))
      (node (ref "U$139") (pin "-") (pinfunction "-_-") (pintype "bidirectional"))
      (node (ref "U$140") (pin "-") (pinfunction "-_-") (pintype "bidirectional"))
      (node (ref "U$141") (pin "-") (pinfunction "-_-") (pintype "bidirectional"))
      (node (ref "U$142") (pin "-") (pinfunction "-_-") (pintype "bidirectional"))
      (node (ref "U$143") (pin "-") (pinfunction "-_-") (pintype "bidirectional"))
      (node (ref "U$144") (pin "-") (pinfunction "-_-") (pintype "bidirectional"))
      (node (ref "U$257") (pin "P$15") (pinfunction "15_P$15") (pintype "bidirectional"))
    )
    (net (code "16") (name "Net-(U$257-16)") (class "Default")
      (node (ref "U$104") (pin "+") (pinfunction "+_+") (pintype "bidirectional"))
      (node (ref "U$120") (pin "+") (pinfunction "+_+") (pintype "bidirectional"))
      (node (ref "U$136") (pin "+") (pinfunction "+_+") (pintype "bidirectional"))
      (node (ref "U$152") (pin "+") (pinfunction "+_+") (pintype "bidirectional"))
      (node (ref "U$168") (pin "+") (pinfunction "+_+") (pintype "bidirectional"))
      (node (ref "U$184") (pin "+") (pinfunction "+_+") (pintype "bidirectional"))
      (node (ref "U$200") (pin "+") (pinfunction "+_+") (pintype "bidirectional"))
      (node (ref "U$216") (pin "+") (pinfunction "+_+") (pintype "bidirectional"))
      (node (ref "U$232") (pin "+") (pinfunction "+_+") (pintype "bidirectional"))
      (node (ref "U$24") (pin "+") (pinfunction "+_+") (pintype "bidirectional"))
      (node (ref "U$248") (pin "+") (pinfunction "+_+") (pintype "bidirectional"))
      (node (ref "U$257") (pin "P$16") (pinfunction "16_P$16") (pintype "bidirectional"))
      (node (ref "U$40") (pin "+") (pinfunction "+_+") (pintype "bidirectional"))
      (node (ref "U$56") (pin "+") (pinfunction "+_+") (pintype "bidirectional"))
      (node (ref "U$72") (pin "+") (pinfunction "+_+") (pintype "bidirectional"))
      (node (ref "U$8") (pin "+") (pinfunction "+_+") (pintype "bidirectional"))
      (node (ref "U$88") (pin "+") (pinfunction "+_+") (pintype "bidirectional"))
    )
    (net (code "17") (name "Net-(U$257-17)") (class "Default")
      (node (ref "U$113") (pin "-") (pinfunction "-_-") (pintype "bidirectional"))
      (node (ref "U$114") (pin "-") (pinfunction "-_-") (pintype "bidirectional"))
      (node (ref "U$115") (pin "-") (pinfunction "-_-") (pintype "bidirectional"))
      (node (ref "U$116") (pin "-") (pinfunction "-_-") (pintype "bidirectional"))
      (node (ref "U$117") (pin "-") (pinfunction "-_-") (pintype "bidirectional"))
      (node (ref "U$118") (pin "-") (pinfunction "-_-") (pintype "bidirectional"))
      (node (ref "U$119") (pin "-") (pinfunction "-_-") (pintype "bidirectional"))
      (node (ref "U$120") (pin "-") (pinfunction "-_-") (pintype "bidirectional"))
      (node (ref "U$121") (pin "-") (pinfunction "-_-") (pintype "bidirectional"))
      (node (ref "U$122") (pin "-") (pinfunction "-_-") (pintype "bidirectional"))
      (node (ref "U$123") (pin "-") (pinfunction "-_-") (pintype "bidirectional"))
      (node (ref "U$124") (pin "-") (pinfunction "-_-") (pintype "bidirectional"))
      (node (ref "U$125") (pin "-") (pinfunction "-_-") (pintype "bidirectional"))
      (node (ref "U$126") (pin "-") (pinfunction "-_-") (pintype "bidirectional"))
      (node (ref "U$127") (pin "-") (pinfunction "-_-") (pintype "bidirectional"))
      (node (ref "U$128") (pin "-") (pinfunction "-_-") (pintype "bidirectional"))
      (node (ref "U$257") (pin "P$17") (pinfunction "17_P$17") (pintype "bidirectional"))
    )
    (net (code "18") (name "Net-(U$257-18)") (class "Default")
      (node (ref "U$105") (pin "+") (pinfunction "+_+") (pintype "bidirectional"))
      (node (ref "U$121") (pin "+") (pinfunction "+_+") (pintype "bidirectional"))
      (node (ref "U$137") (pin "+") (pinfunction "+_+") (pintype "bidirectional"))
      (node (ref "U$153") (pin "+") (pinfunction "+_+") (pintype "bidirectional"))
      (node (ref "U$169") (pin "+") (pinfunction "+_+") (pintype "bidirectional"))
      (node (ref "U$185") (pin "+") (pinfunction "+_+") (pintype "bidirectional"))
      (node (ref "U$201") (pin "+") (pinfunction "+_+") (pintype "bidirectional"))
      (node (ref "U$217") (pin "+") (pinfunction "+_+") (pintype "bidirectional"))
      (node (ref "U$233") (pin "+") (pinfunction "+_+") (pintype "bidirectional"))
      (node (ref "U$249") (pin "+") (pinfunction "+_+") (pintype "bidirectional"))
      (node (ref "U$25") (pin "+") (pinfunction "+_+") (pintype "bidirectional"))
      (node (ref "U$257") (pin "P$18") (pinfunction "18_P$18") (pintype "bidirectional"))
      (node (ref "U$41") (pin "+") (pinfunction "+_+") (pintype "bidirectional"))
      (node (ref "U$57") (pin "+") (pinfunction "+_+") (pintype "bidirectional"))
      (node (ref "U$73") (pin "+") (pinfunction "+_+") (pintype "bidirectional"))
      (node (ref "U$89") (pin "+") (pinfunction "+_+") (pintype "bidirectional"))
      (node (ref "U$9") (pin "+") (pinfunction "+_+") (pintype "bidirectional"))
    )
    (net (code "19") (name "Net-(U$257-19)") (class "Default")
      (node (ref "U$100") (pin "-") (pinfunction "-_-") (pintype "bidirectional"))
      (node (ref "U$101") (pin "-") (pinfunction "-_-") (pintype "bidirectional"))
      (node (ref "U$102") (pin "-") (pinfunction "-_-") (pintype "bidirectional"))
      (node (ref "U$103") (pin "-") (pinfunction "-_-") (pintype "bidirectional"))
      (node (ref "U$104") (pin "-") (pinfunction "-_-") (pintype "bidirectional"))
      (node (ref "U$105") (pin "-") (pinfunction "-_-") (pintype "bidirectional"))
      (node (ref "U$106") (pin "-") (pinfunction "-_-") (pintype "bidirectional"))
      (node (ref "U$107") (pin "-") (pinfunction "-_-") (pintype "bidirectional"))
      (node (ref "U$108") (pin "-") (pinfunction "-_-") (pintype "bidirectional"))
      (node (ref "U$109") (pin "-") (pinfunction "-_-") (pintype "bidirectional"))
      (node (ref "U$110") (pin "-") (pinfunction "-_-") (pintype "bidirectional"))
      (node (ref "U$111") (pin "-") (pinfunction "-_-") (pintype "bidirectional"))
      (node (ref "U$112") (pin "-") (pinfunction "-_-") (pintype "bidirectional"))
      (node (ref "U$257") (pin "P$19") (pinfunction "19_P$19") (pintype "bidirectional"))
      (node (ref "U$97") (pin "-") (pinfunction "-_-") (pintype "bidirectional"))
      (node (ref "U$98") (pin "-") (pinfunction "-_-") (pintype "bidirectional"))
      (node (ref "U$99") (pin "-") (pinfunction "-_-") (pintype "bidirectional"))
    )
    (net (code "20") (name "Net-(U$257-20)") (class "Default")
      (node (ref "U$10") (pin "+") (pinfunction "+_+") (pintype "bidirectional"))
      (node (ref "U$106") (pin "+") (pinfunction "+_+") (pintype "bidirectional"))
      (node (ref "U$122") (pin "+") (pinfunction "+_+") (pintype "bidirectional"))
      (node (ref "U$138") (pin "+") (pinfunction "+_+") (pintype "bidirectional"))
      (node (ref "U$154") (pin "+") (pinfunction "+_+") (pintype "bidirectional"))
      (node (ref "U$170") (pin "+") (pinfunction "+_+") (pintype "bidirectional"))
      (node (ref "U$186") (pin "+") (pinfunction "+_+") (pintype "bidirectional"))
      (node (ref "U$202") (pin "+") (pinfunction "+_+") (pintype "bidirectional"))
      (node (ref "U$218") (pin "+") (pinfunction "+_+") (pintype "bidirectional"))
      (node (ref "U$234") (pin "+") (pinfunction "+_+") (pintype "bidirectional"))
      (node (ref "U$250") (pin "+") (pinfunction "+_+") (pintype "bidirectional"))
      (node (ref "U$257") (pin "P$20") (pinfunction "20_P$20") (pintype "bidirectional"))
      (node (ref "U$26") (pin "+") (pinfunction "+_+") (pintype "bidirectional"))
      (node (ref "U$42") (pin "+") (pinfunction "+_+") (pintype "bidirectional"))
      (node (ref "U$58") (pin "+") (pinfunction "+_+") (pintype "bidirectional"))
      (node (ref "U$74") (pin "+") (pinfunction "+_+") (pintype "bidirectional"))
      (node (ref "U$90") (pin "+") (pinfunction "+_+") (pintype "bidirectional"))
    )
    (net (code "21") (name "Net-(U$257-21)") (class "Default")
      (node (ref "U$257") (pin "P$21") (pinfunction "21_P$21") (pintype "bidirectional"))
      (node (ref "U$81") (pin "-") (pinfunction "-_-") (pintype "bidirectional"))
      (node (ref "U$82") (pin "-") (pinfunction "-_-") (pintype "bidirectional"))
      (node (ref "U$83") (pin "-") (pinfunction "-_-") (pintype "bidirectional"))
      (node (ref "U$84") (pin "-") (pinfunction "-_-") (pintype "bidirectional"))
      (node (ref "U$85") (pin "-") (pinfunction "-_-") (pintype "bidirectional"))
      (node (ref "U$86") (pin "-") (pinfunction "-_-") (pintype "bidirectional"))
      (node (ref "U$87") (pin "-") (pinfunction "-_-") (pintype "bidirectional"))
      (node (ref "U$88") (pin "-") (pinfunction "-_-") (pintype "bidirectional"))
      (node (ref "U$89") (pin "-") (pinfunction "-_-") (pintype "bidirectional"))
      (node (ref "U$90") (pin "-") (pinfunction "-_-") (pintype "bidirectional"))
      (node (ref "U$91") (pin "-") (pinfunction "-_-") (pintype "bidirectional"))
      (node (ref "U$92") (pin "-") (pinfunction "-_-") (pintype "bidirectional"))
      (node (ref "U$93") (pin "-") (pinfunction "-_-") (pintype "bidirectional"))
      (node (ref "U$94") (pin "-") (pinfunction "-_-") (pintype "bidirectional"))
      (node (ref "U$95") (pin "-") (pinfunction "-_-") (pintype "bidirectional"))
      (node (ref "U$96") (pin "-") (pinfunction "-_-") (pintype "bidirectional"))
    )
    (net (code "22") (name "Net-(U$257-22)") (class "Default")
      (node (ref "U$107") (pin "+") (pinfunction "+_+") (pintype "bidirectional"))
      (node (ref "U$11") (pin "+") (pinfunction "+_+") (pintype "bidirectional"))
      (node (ref "U$123") (pin "+") (pinfunction "+_+") (pintype "bidirectional"))
      (node (ref "U$139") (pin "+") (pinfunction "+_+") (pintype "bidirectional"))
      (node (ref "U$155") (pin "+") (pinfunction "+_+") (pintype "bidirectional"))
      (node (ref "U$171") (pin "+") (pinfunction "+_+") (pintype "bidirectional"))
      (node (ref "U$187") (pin "+") (pinfunction "+_+") (pintype "bidirectional"))
      (node (ref "U$203") (pin "+") (pinfunction "+_+") (pintype "bidirectional"))
      (node (ref "U$219") (pin "+") (pinfunction "+_+") (pintype "bidirectional"))
      (node (ref "U$235") (pin "+") (pinfunction "+_+") (pintype "bidirectional"))
      (node (ref "U$251") (pin "+") (pinfunction "+_+") (pintype "bidirectional"))
      (node (ref "U$257") (pin "P$22") (pinfunction "22_P$22") (pintype "bidirectional"))
      (node (ref "U$27") (pin "+") (pinfunction "+_+") (pintype "bidirectional"))
      (node (ref "U$43") (pin "+") (pinfunction "+_+") (pintype "bidirectional"))
      (node (ref "U$59") (pin "+") (pinfunction "+_+") (pintype "bidirectional"))
      (node (ref "U$75") (pin "+") (pinfunction "+_+") (pintype "bidirectional"))
      (node (ref "U$91") (pin "+") (pinfunction "+_+") (pintype "bidirectional"))
    )
    (net (code "23") (name "Net-(U$257-23)") (class "Default")
      (node (ref "U$257") (pin "P$23") (pinfunction "23_P$23") (pintype "bidirectional"))
      (node (ref "U$65") (pin "-") (pinfunction "-_-") (pintype "bidirectional"))
      (node (ref "U$66") (pin "-") (pinfunction "-_-") (pintype "bidirectional"))
      (node (ref "U$67") (pin "-") (pinfunction "-_-") (pintype "bidirectional"))
      (node (ref "U$68") (pin "-") (pinfunction "-_-") (pintype "bidirectional"))
      (node (ref "U$69") (pin "-") (pinfunction "-_-") (pintype "bidirectional"))
      (node (ref "U$70") (pin "-") (pinfunction "-_-") (pintype "bidirectional"))
      (node (ref "U$71") (pin "-") (pinfunction "-_-") (pintype "bidirectional"))
      (node (ref "U$72") (pin "-") (pinfunction "-_-") (pintype "bidirectional"))
      (node (ref "U$73") (pin "-") (pinfunction "-_-") (pintype "bidirectional"))
      (node (ref "U$74") (pin "-") (pinfunction "-_-") (pintype "bidirectional"))
      (node (ref "U$75") (pin "-") (pinfunction "-_-") (pintype "bidirectional"))
      (node (ref "U$76") (pin "-") (pinfunction "-_-") (pintype "bidirectional"))
      (node (ref "U$77") (pin "-") (pinfunction "-_-") (pintype "bidirectional"))
      (node (ref "U$78") (pin "-") (pinfunction "-_-") (pintype "bidirectional"))
      (node (ref "U$79") (pin "-") (pinfunction "-_-") (pintype "bidirectional"))
      (node (ref "U$80") (pin "-") (pinfunction "-_-") (pintype "bidirectional"))
    )
    (net (code "24") (name "Net-(U$257-24)") (class "Default")
      (node (ref "U$108") (pin "+") (pinfunction "+_+") (pintype "bidirectional"))
      (node (ref "U$12") (pin "+") (pinfunction "+_+") (pintype "bidirectional"))
      (node (ref "U$124") (pin "+") (pinfunction "+_+") (pintype "bidirectional"))
      (node (ref "U$140") (pin "+") (pinfunction "+_+") (pintype "bidirectional"))
      (node (ref "U$156") (pin "+") (pinfunction "+_+") (pintype "bidirectional"))
      (node (ref "U$172") (pin "+") (pinfunction "+_+") (pintype "bidirectional"))
      (node (ref "U$188") (pin "+") (pinfunction "+_+") (pintype "bidirectional"))
      (node (ref "U$204") (pin "+") (pinfunction "+_+") (pintype "bidirectional"))
      (node (ref "U$220") (pin "+") (pinfunction "+_+") (pintype "bidirectional"))
      (node (ref "U$236") (pin "+") (pinfunction "+_+") (pintype "bidirectional"))
      (node (ref "U$252") (pin "+") (pinfunction "+_+") (pintype "bidirectional"))
      (node (ref "U$257") (pin "P$24") (pinfunction "24_P$24") (pintype "bidirectional"))
      (node (ref "U$28") (pin "+") (pinfunction "+_+") (pintype "bidirectional"))
      (node (ref "U$44") (pin "+") (pinfunction "+_+") (pintype "bidirectional"))
      (node (ref "U$60") (pin "+") (pinfunction "+_+") (pintype "bidirectional"))
      (node (ref "U$76") (pin "+") (pinfunction "+_+") (pintype "bidirectional"))
      (node (ref "U$92") (pin "+") (pinfunction "+_+") (pintype "bidirectional"))
    )
    (net (code "25") (name "Net-(U$257-25)") (class "Default")
      (node (ref "U$257") (pin "P$25") (pinfunction "25_P$25") (pintype "bidirectional"))
      (node (ref "U$49") (pin "-") (pinfunction "-_-") (pintype "bidirectional"))
      (node (ref "U$50") (pin "-") (pinfunction "-_-") (pintype "bidirectional"))
      (node (ref "U$51") (pin "-") (pinfunction "-_-") (pintype "bidirectional"))
      (node (ref "U$52") (pin "-") (pinfunction "-_-") (pintype "bidirectional"))
      (node (ref "U$53") (pin "-") (pinfunction "-_-") (pintype "bidirectional"))
      (node (ref "U$54") (pin "-") (pinfunction "-_-") (pintype "bidirectional"))
      (node (ref "U$55") (pin "-") (pinfunction "-_-") (pintype "bidirectional"))
      (node (ref "U$56") (pin "-") (pinfunction "-_-") (pintype "bidirectional"))
      (node (ref "U$57") (pin "-") (pinfunction "-_-") (pintype "bidirectional"))
      (node (ref "U$58") (pin "-") (pinfunction "-_-") (pintype "bidirectional"))
      (node (ref "U$59") (pin "-") (pinfunction "-_-") (pintype "bidirectional"))
      (node (ref "U$60") (pin "-") (pinfunction "-_-") (pintype "bidirectional"))
      (node (ref "U$61") (pin "-") (pinfunction "-_-") (pintype "bidirectional"))
      (node (ref "U$62") (pin "-") (pinfunction "-_-") (pintype "bidirectional"))
      (node (ref "U$63") (pin "-") (pinfunction "-_-") (pintype "bidirectional"))
      (node (ref "U$64") (pin "-") (pinfunction "-_-") (pintype "bidirectional"))
    )
    (net (code "26") (name "Net-(U$257-26)") (class "Default")
      (node (ref "U$109") (pin "+") (pinfunction "+_+") (pintype "bidirectional"))
      (node (ref "U$125") (pin "+") (pinfunction "+_+") (pintype "bidirectional"))
      (node (ref "U$13") (pin "+") (pinfunction "+_+") (pintype "bidirectional"))
      (node (ref "U$141") (pin "+") (pinfunction "+_+") (pintype "bidirectional"))
      (node (ref "U$157") (pin "+") (pinfunction "+_+") (pintype "bidirectional"))
      (node (ref "U$173") (pin "+") (pinfunction "+_+") (pintype "bidirectional"))
      (node (ref "U$189") (pin "+") (pinfunction "+_+") (pintype "bidirectional"))
      (node (ref "U$205") (pin "+") (pinfunction "+_+") (pintype "bidirectional"))
      (node (ref "U$221") (pin "+") (pinfunction "+_+") (pintype "bidirectional"))
      (node (ref "U$237") (pin "+") (pinfunction "+_+") (pintype "bidirectional"))
      (node (ref "U$253") (pin "+") (pinfunction "+_+") (pintype "bidirectional"))
      (node (ref "U$257") (pin "P$26") (pinfunction "26_P$26") (pintype "bidirectional"))
      (node (ref "U$29") (pin "+") (pinfunction "+_+") (pintype "bidirectional"))
      (node (ref "U$45") (pin "+") (pinfunction "+_+") (pintype "bidirectional"))
      (node (ref "U$61") (pin "+") (pinfunction "+_+") (pintype "bidirectional"))
      (node (ref "U$77") (pin "+") (pinfunction "+_+") (pintype "bidirectional"))
      (node (ref "U$93") (pin "+") (pinfunction "+_+") (pintype "bidirectional"))
    )
    (net (code "27") (name "Net-(U$257-27)") (class "Default")
      (node (ref "U$257") (pin "P$27") (pinfunction "27_P$27") (pintype "bidirectional"))
      (node (ref "U$33") (pin "-") (pinfunction "-_-") (pintype "bidirectional"))
      (node (ref "U$34") (pin "-") (pinfunction "-_-") (pintype "bidirectional"))
      (node (ref "U$35") (pin "-") (pinfunction "-_-") (pintype "bidirectional"))
      (node (ref "U$36") (pin "-") (pinfunction "-_-") (pintype "bidirectional"))
      (node (ref "U$37") (pin "-") (pinfunction "-_-") (pintype "bidirectional"))
      (node (ref "U$38") (pin "-") (pinfunction "-_-") (pintype "bidirectional"))
      (node (ref "U$39") (pin "-") (pinfunction "-_-") (pintype "bidirectional"))
      (node (ref "U$40") (pin "-") (pinfunction "-_-") (pintype "bidirectional"))
      (node (ref "U$41") (pin "-") (pinfunction "-_-") (pintype "bidirectional"))
      (node (ref "U$42") (pin "-") (pinfunction "-_-") (pintype "bidirectional"))
      (node (ref "U$43") (pin "-") (pinfunction "-_-") (pintype "bidirectional"))
      (node (ref "U$44") (pin "-") (pinfunction "-_-") (pintype "bidirectional"))
      (node (ref "U$45") (pin "-") (pinfunction "-_-") (pintype "bidirectional"))
      (node (ref "U$46") (pin "-") (pinfunction "-_-") (pintype "bidirectional"))
      (node (ref "U$47") (pin "-") (pinfunction "-_-") (pintype "bidirectional"))
      (node (ref "U$48") (pin "-") (pinfunction "-_-") (pintype "bidirectional"))
    )
    (net (code "28") (name "Net-(U$257-28)") (class "Default")
      (node (ref "U$110") (pin "+") (pinfunction "+_+") (pintype "bidirectional"))
      (node (ref "U$126") (pin "+") (pinfunction "+_+") (pintype "bidirectional"))
      (node (ref "U$14") (pin "+") (pinfunction "+_+") (pintype "bidirectional"))
      (node (ref "U$142") (pin "+") (pinfunction "+_+") (pintype "bidirectional"))
      (node (ref "U$158") (pin "+") (pinfunction "+_+") (pintype "bidirectional"))
      (node (ref "U$174") (pin "+") (pinfunction "+_+") (pintype "bidirectional"))
      (node (ref "U$190") (pin "+") (pinfunction "+_+") (pintype "bidirectional"))
      (node (ref "U$206") (pin "+") (pinfunction "+_+") (pintype "bidirectional"))
      (node (ref "U$222") (pin "+") (pinfunction "+_+") (pintype "bidirectional"))
      (node (ref "U$238") (pin "+") (pinfunction "+_+") (pintype "bidirectional"))
      (node (ref "U$254") (pin "+") (pinfunction "+_+") (pintype "bidirectional"))
      (node (ref "U$257") (pin "P$28") (pinfunction "28_P$28") (pintype "bidirectional"))
      (node (ref "U$30") (pin "+") (pinfunction "+_+") (pintype "bidirectional"))
      (node (ref "U$46") (pin "+") (pinfunction "+_+") (pintype "bidirectional"))
      (node (ref "U$62") (pin "+") (pinfunction "+_+") (pintype "bidirectional"))
      (node (ref "U$78") (pin "+") (pinfunction "+_+") (pintype "bidirectional"))
      (node (ref "U$94") (pin "+") (pinfunction "+_+") (pintype "bidirectional"))
    )
    (net (code "29") (name "Net-(U$257-29)") (class "Default")
      (node (ref "U$17") (pin "-") (pinfunction "-_-") (pintype "bidirectional"))
      (node (ref "U$18") (pin "-") (pinfunction "-_-") (pintype "bidirectional"))
      (node (ref "U$19") (pin "-") (pinfunction "-_-") (pintype "bidirectional"))
      (node (ref "U$20") (pin "-") (pinfunction "-_-") (pintype "bidirectional"))
      (node (ref "U$21") (pin "-") (pinfunction "-_-") (pintype "bidirectional"))
      (node (ref "U$22") (pin "-") (pinfunction "-_-") (pintype "bidirectional"))
      (node (ref "U$23") (pin "-") (pinfunction "-_-") (pintype "bidirectional"))
      (node (ref "U$24") (pin "-") (pinfunction "-_-") (pintype "bidirectional"))
      (node (ref "U$25") (pin "-") (pinfunction "-_-") (pintype "bidirectional"))
      (node (ref "U$257") (pin "P$29") (pinfunction "29_P$29") (pintype "bidirectional"))
      (node (ref "U$26") (pin "-") (pinfunction "-_-") (pintype "bidirectional"))
      (node (ref "U$27") (pin "-") (pinfunction "-_-") (pintype "bidirectional"))
      (node (ref "U$28") (pin "-") (pinfunction "-_-") (pintype "bidirectional"))
      (node (ref "U$29") (pin "-") (pinfunction "-_-") (pintype "bidirectional"))
      (node (ref "U$30") (pin "-") (pinfunction "-_-") (pintype "bidirectional"))
      (node (ref "U$31") (pin "-") (pinfunction "-_-") (pintype "bidirectional"))
      (node (ref "U$32") (pin "-") (pinfunction "-_-") (pintype "bidirectional"))
    )
    (net (code "30") (name "Net-(U$257-30)") (class "Default")
      (node (ref "U$111") (pin "+") (pinfunction "+_+") (pintype "bidirectional"))
      (node (ref "U$127") (pin "+") (pinfunction "+_+") (pintype "bidirectional"))
      (node (ref "U$143") (pin "+") (pinfunction "+_+") (pintype "bidirectional"))
      (node (ref "U$15") (pin "+") (pinfunction "+_+") (pintype "bidirectional"))
      (node (ref "U$159") (pin "+") (pinfunction "+_+") (pintype "bidirectional"))
      (node (ref "U$175") (pin "+") (pinfunction "+_+") (pintype "bidirectional"))
      (node (ref "U$191") (pin "+") (pinfunction "+_+") (pintype "bidirectional"))
      (node (ref "U$207") (pin "+") (pinfunction "+_+") (pintype "bidirectional"))
      (node (ref "U$223") (pin "+") (pinfunction "+_+") (pintype "bidirectional"))
      (node (ref "U$239") (pin "+") (pinfunction "+_+") (pintype "bidirectional"))
      (node (ref "U$255") (pin "+") (pinfunction "+_+") (pintype "bidirectional"))
      (node (ref "U$257") (pin "P$30") (pinfunction "30_P$30") (pintype "bidirectional"))
      (node (ref "U$31") (pin "+") (pinfunction "+_+") (pintype "bidirectional"))
      (node (ref "U$47") (pin "+") (pinfunction "+_+") (pintype "bidirectional"))
      (node (ref "U$63") (pin "+") (pinfunction "+_+") (pintype "bidirectional"))
      (node (ref "U$79") (pin "+") (pinfunction "+_+") (pintype "bidirectional"))
      (node (ref "U$95") (pin "+") (pinfunction "+_+") (pintype "bidirectional"))
    )
    (net (code "31") (name "Net-(U$257-31)") (class "Default")
      (node (ref "U$1") (pin "-") (pinfunction "-_-") (pintype "bidirectional"))
      (node (ref "U$10") (pin "-") (pinfunction "-_-") (pintype "bidirectional"))
      (node (ref "U$11") (pin "-") (pinfunction "-_-") (pintype "bidirectional"))
      (node (ref "U$12") (pin "-") (pinfunction "-_-") (pintype "bidirectional"))
      (node (ref "U$13") (pin "-") (pinfunction "-_-") (pintype "bidirectional"))
      (node (ref "U$14") (pin "-") (pinfunction "-_-") (pintype "bidirectional"))
      (node (ref "U$15") (pin "-") (pinfunction "-_-") (pintype "bidirectional"))
      (node (ref "U$16") (pin "-") (pinfunction "-_-") (pintype "bidirectional"))
      (node (ref "U$2") (pin "-") (pinfunction "-_-") (pintype "bidirectional"))
      (node (ref "U$257") (pin "P$31") (pinfunction "31_P$31") (pintype "bidirectional"))
      (node (ref "U$3") (pin "-") (pinfunction "-_-") (pintype "bidirectional"))
      (node (ref "U$4") (pin "-") (pinfunction "-_-") (pintype "bidirectional"))
      (node (ref "U$5") (pin "-") (pinfunction "-_-") (pintype "bidirectional"))
      (node (ref "U$6") (pin "-") (pinfunction "-_-") (pintype "bidirectional"))
      (node (ref "U$7") (pin "-") (pinfunction "-_-") (pintype "bidirectional"))
      (node (ref "U$8") (pin "-") (pinfunction "-_-") (pintype "bidirectional"))
      (node (ref "U$9") (pin "-") (pinfunction "-_-") (pintype "bidirectional"))
    )
    (net (code "32") (name "Net-(U$257-32)") (class "Default")
      (node (ref "U$112") (pin "+") (pinfunction "+_+") (pintype "bidirectional"))
      (node (ref "U$128") (pin "+") (pinfunction "+_+") (pintype "bidirectional"))
      (node (ref "U$144") (pin "+") (pinfunction "+_+") (pintype "bidirectional"))
      (node (ref "U$16") (pin "+") (pinfunction "+_+") (pintype "bidirectional"))
      (node (ref "U$160") (pin "+") (pinfunction "+_+") (pintype "bidirectional"))
      (node (ref "U$176") (pin "+") (pinfunction "+_+") (pintype "bidirectional"))
      (node (ref "U$192") (pin "+") (pinfunction "+_+") (pintype "bidirectional"))
      (node (ref "U$208") (pin "+") (pinfunction "+_+") (pintype "bidirectional"))
      (node (ref "U$224") (pin "+") (pinfunction "+_+") (pintype "bidirectional"))
      (node (ref "U$240") (pin "+") (pinfunction "+_+") (pintype "bidirectional"))
      (node (ref "U$256") (pin "+") (pinfunction "+_+") (pintype "bidirectional"))
      (node (ref "U$257") (pin "P$32") (pinfunction "32_P$32") (pintype "bidirectional"))
      (node (ref "U$32") (pin "+") (pinfunction "+_+") (pintype "bidirectional"))
      (node (ref "U$48") (pin "+") (pinfunction "+_+") (pintype "bidirectional"))
      (node (ref "U$64") (pin "+") (pinfunction "+_+") (pintype "bidirectional"))
      (node (ref "U$80") (pin "+") (pinfunction "+_+") (pintype "bidirectional"))
      (node (ref "U$96") (pin "+") (pinfunction "+_+") (pintype "bidirectional"))
    )
  )
)
